# Main.net
KiCad netlist of a schematic drawn in Altium Designer
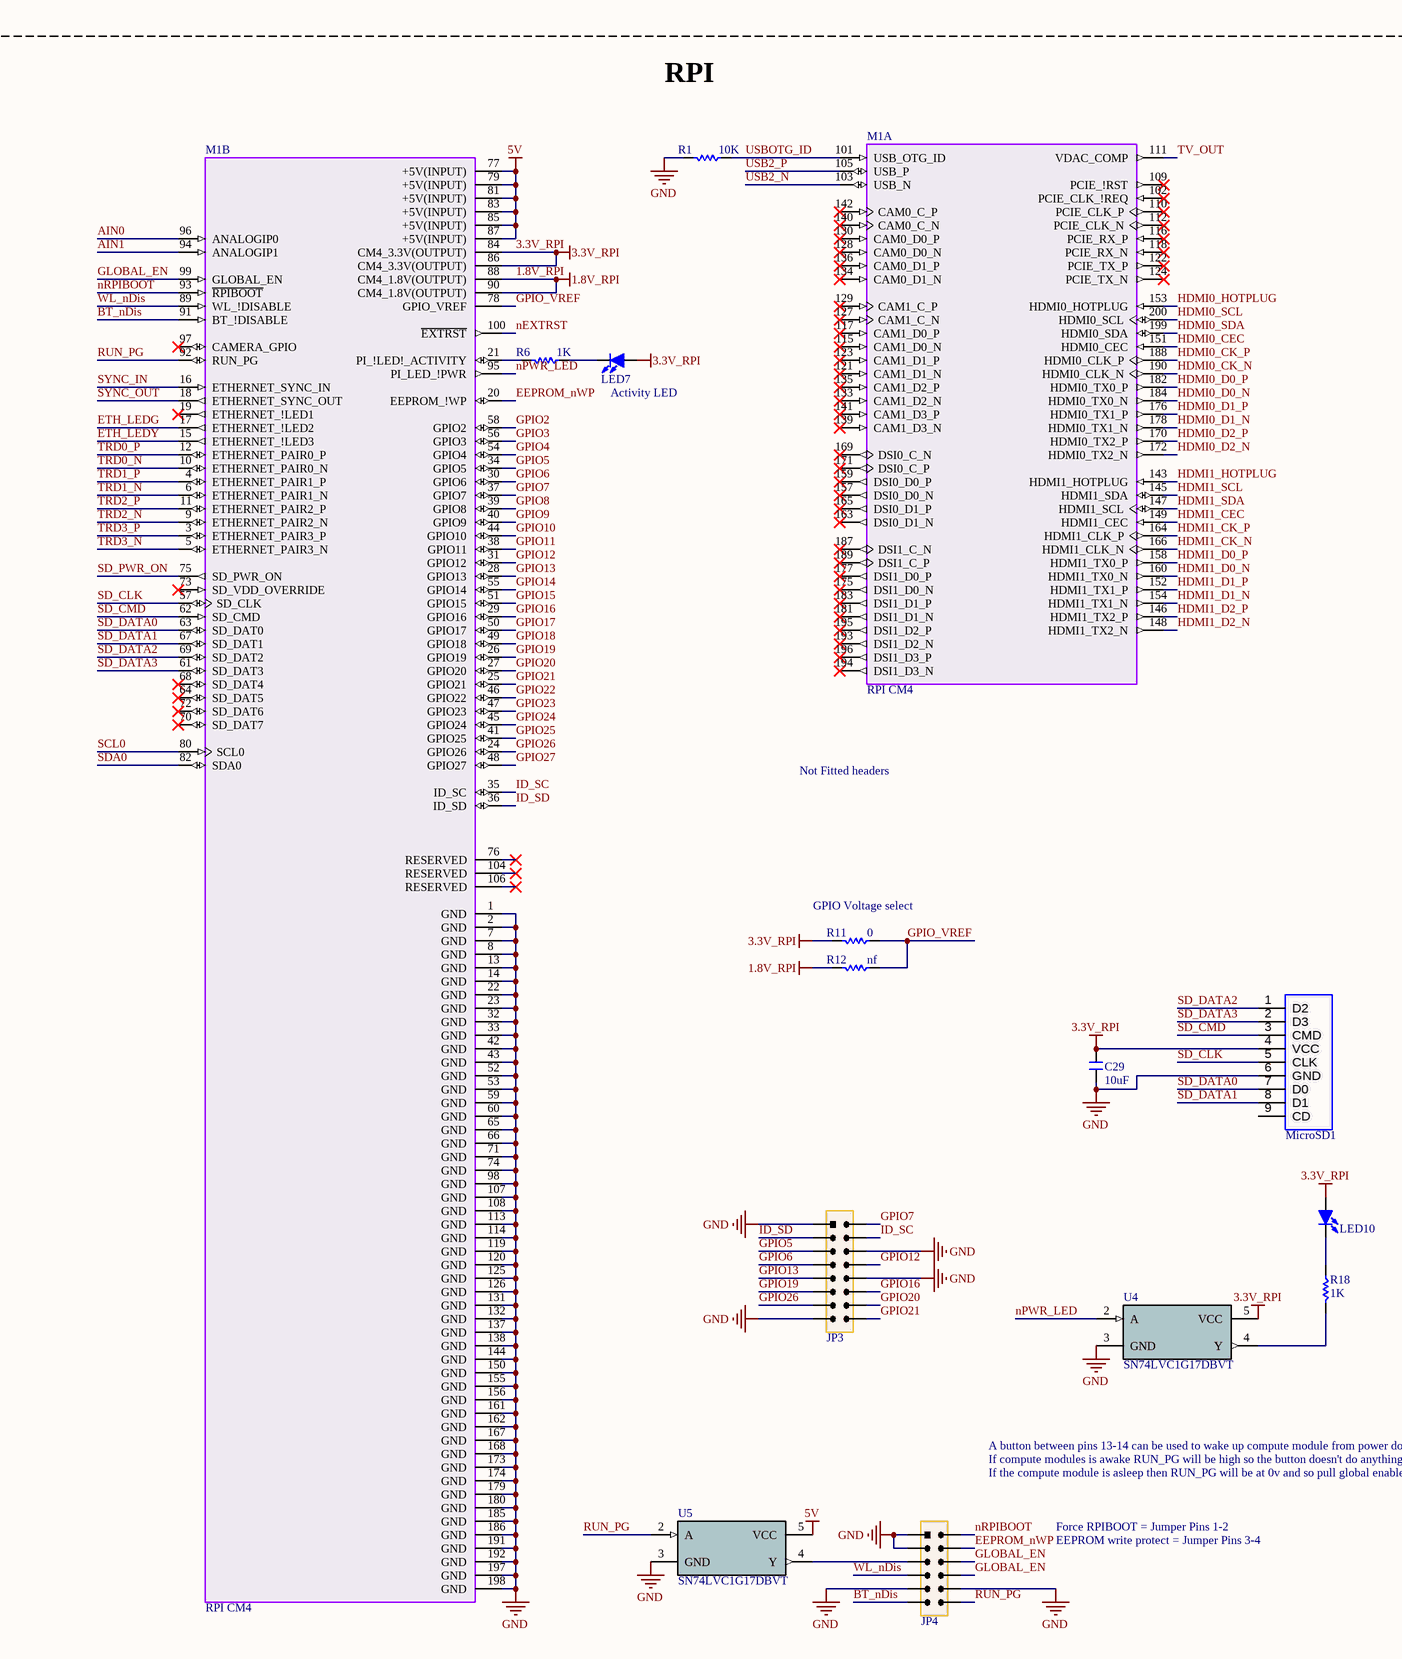
[diagram p0: Main.SchDoc, top left]
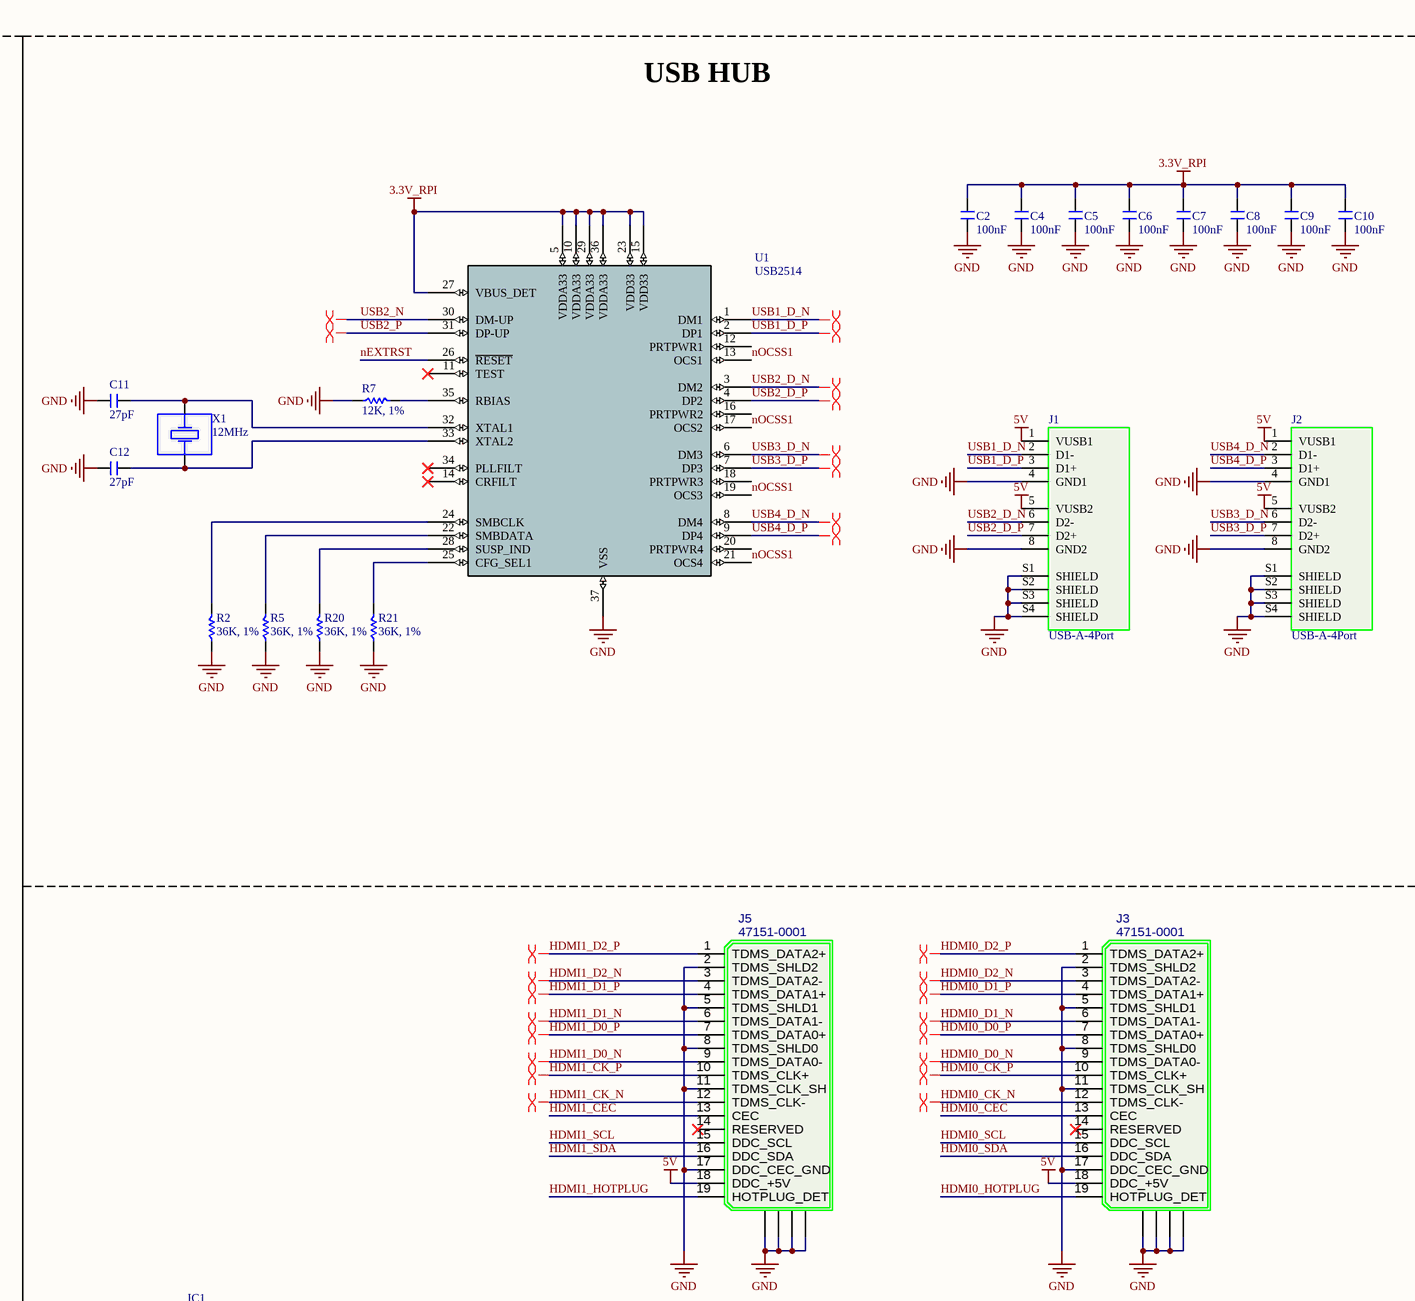
[diagram p1: Main.SchDoc, top middle]
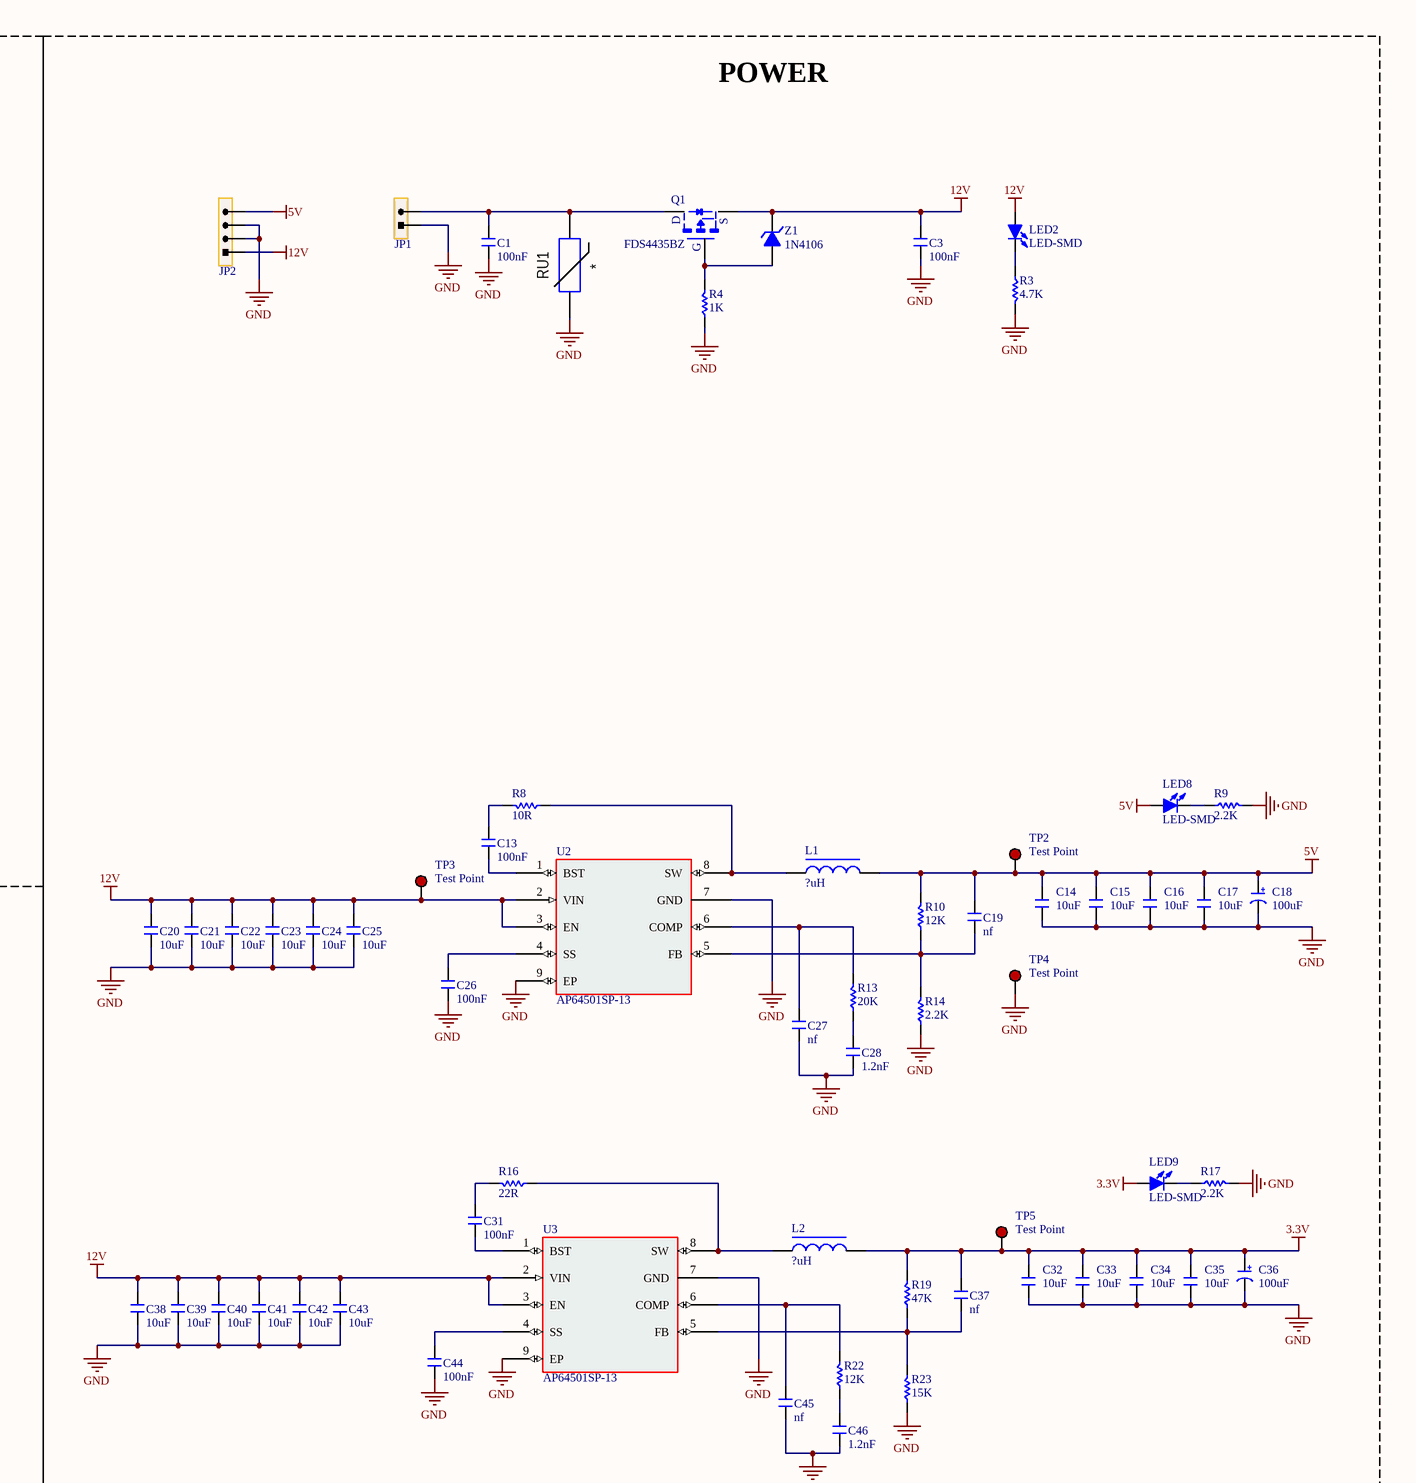
[diagram p2: Main.SchDoc, top right]
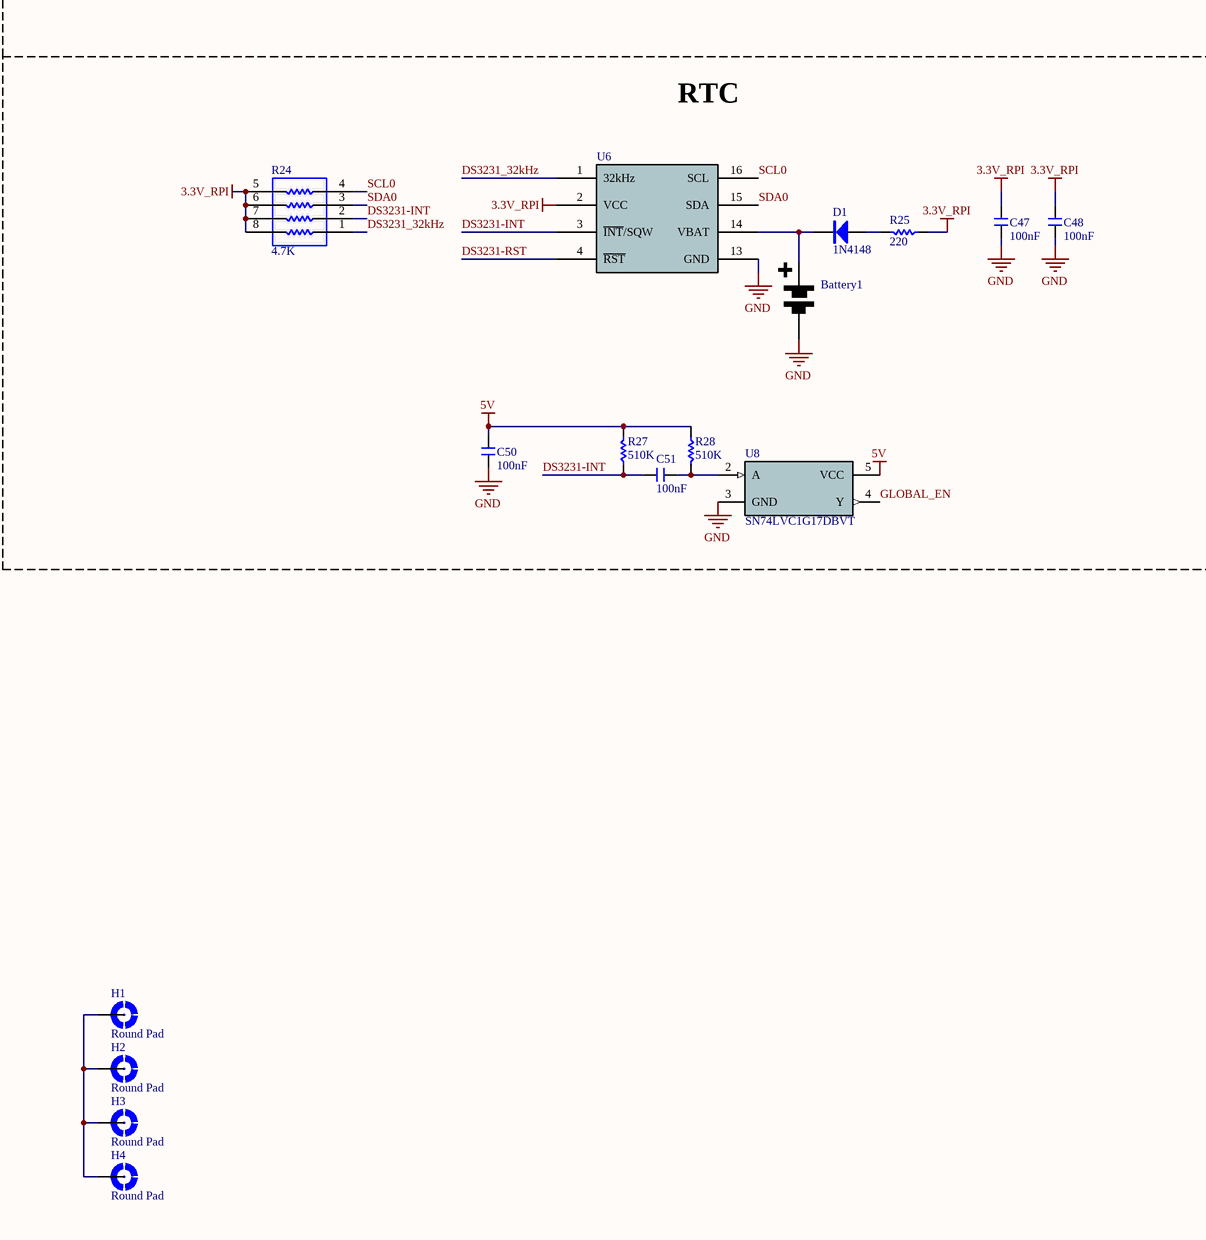
[diagram p3: Main.SchDoc, bottom left]
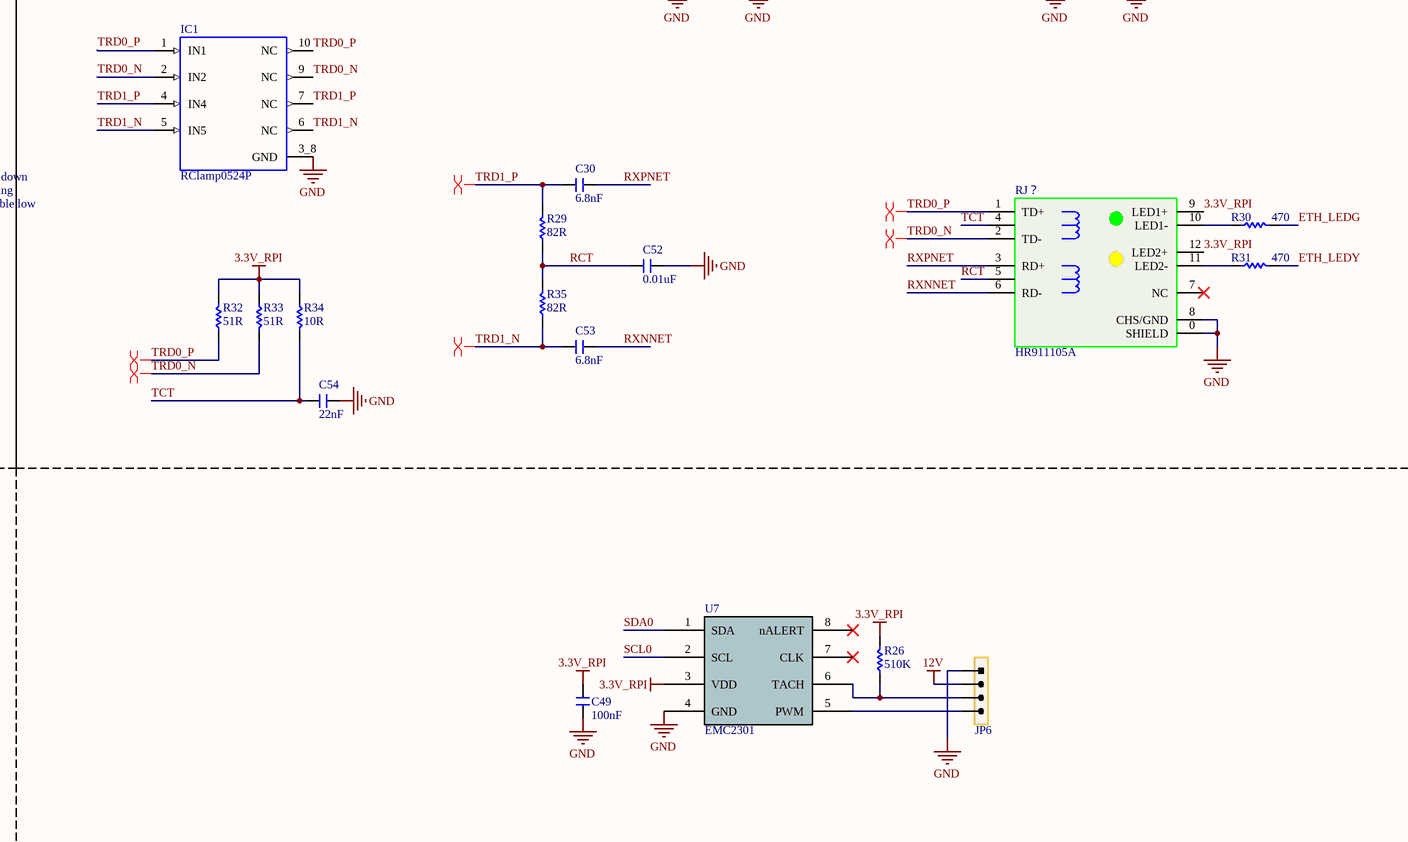
[diagram p4: Main.SchDoc, bottom middle]

(export (version "E")
  (design (tool "Eeschema 10.0.6"))
  (components
    (comp (ref "Battery1")
      (value "Battery Button Cell")
      (footprint "CR2032")
      (description "Mini Battery")
      (libsource (lib "Battery Holder") (part "Battery Button Cell"))
    )
    (comp (ref "C1")
      (value "100nF")
      (footprint "C 0805")
      (description "Non-polar patch capacitor")
      (fields (field (name "版权归属") "源创客"))
      (libsource (lib "") (part "C_1"))
    )
    (comp (ref "C2")
      (value "100nF")
      (footprint "C 0805")
      (description "Non-polar patch capacitor")
      (fields (field (name "版权归属") "源创客"))
      (libsource (lib "Passive (Resistor-Capacitor-Inductor-Veristor-Ferrite)") (part "C"))
    )
    (comp (ref "C3")
      (value "100nF")
      (footprint "C 0805")
      (description "Non-polar patch capacitor")
      (fields (field (name "版权归属") "源创客"))
      (libsource (lib "") (part "C_1"))
    )
    (comp (ref "C4")
      (value "100nF")
      (footprint "C 0805")
      (description "Non-polar patch capacitor")
      (fields (field (name "版权归属") "源创客"))
      (libsource (lib "Passive (Resistor-Capacitor-Inductor-Veristor-Ferrite)") (part "C"))
    )
    (comp (ref "C5")
      (value "100nF")
      (footprint "C 0805")
      (description "Non-polar patch capacitor")
      (fields (field (name "版权归属") "源创客"))
      (libsource (lib "Passive (Resistor-Capacitor-Inductor-Veristor-Ferrite)") (part "C"))
    )
    (comp (ref "C6")
      (value "100nF")
      (footprint "C 0805")
      (description "Non-polar patch capacitor")
      (fields (field (name "版权归属") "源创客"))
      (libsource (lib "Passive (Resistor-Capacitor-Inductor-Veristor-Ferrite)") (part "C"))
    )
    (comp (ref "C7")
      (value "100nF")
      (footprint "C 0805")
      (description "Non-polar patch capacitor")
      (fields (field (name "版权归属") "源创客"))
      (libsource (lib "Passive (Resistor-Capacitor-Inductor-Veristor-Ferrite)") (part "C"))
    )
    (comp (ref "C8")
      (value "100nF")
      (footprint "C 0805")
      (description "Non-polar patch capacitor")
      (fields (field (name "版权归属") "源创客"))
      (libsource (lib "Passive (Resistor-Capacitor-Inductor-Veristor-Ferrite)") (part "C"))
    )
    (comp (ref "C9")
      (value "100nF")
      (footprint "C 0805")
      (description "Non-polar patch capacitor")
      (fields (field (name "版权归属") "源创客"))
      (libsource (lib "Passive (Resistor-Capacitor-Inductor-Veristor-Ferrite)") (part "C"))
    )
    (comp (ref "C10")
      (value "100nF")
      (footprint "C 0805")
      (description "Non-polar patch capacitor")
      (fields (field (name "版权归属") "源创客"))
      (libsource (lib "Passive (Resistor-Capacitor-Inductor-Veristor-Ferrite)") (part "C"))
    )
    (comp (ref "C11")
      (value "27pF")
      (footprint "C 0805")
      (description "Non-polar patch capacitor")
      (fields (field (name "版权归属") "源创客"))
      (libsource (lib "Passive (Resistor-Capacitor-Inductor-Veristor-Ferrite)") (part "C"))
    )
    (comp (ref "C12")
      (value "27pF")
      (footprint "C 0805")
      (description "Non-polar patch capacitor")
      (fields (field (name "版权归属") "源创客"))
      (libsource (lib "Passive (Resistor-Capacitor-Inductor-Veristor-Ferrite)") (part "C"))
    )
    (comp (ref "C13")
      (value "100nF")
      (footprint "C 0805")
      (description "Non-polar patch capacitor")
      (fields (field (name "版权归属") "源创客"))
      (libsource (lib "") (part "C_1"))
    )
    (comp (ref "C14")
      (value "10uF")
      (footprint "C 0805")
      (description "Non-polar patch capacitor")
      (fields (field (name "版权归属") "源创客"))
      (libsource (lib "") (part "C_1"))
    )
    (comp (ref "C15")
      (value "10uF")
      (footprint "C 0805")
      (description "Non-polar patch capacitor")
      (fields (field (name "版权归属") "源创客"))
      (libsource (lib "") (part "C_1"))
    )
    (comp (ref "C16")
      (value "10uF")
      (footprint "C 0805")
      (description "Non-polar patch capacitor")
      (fields (field (name "版权归属") "源创客"))
      (libsource (lib "") (part "C_1"))
    )
    (comp (ref "C17")
      (value "10uF")
      (footprint "C 0805")
      (description "Non-polar patch capacitor")
      (fields (field (name "版权归属") "源创客"))
      (libsource (lib "") (part "C_1"))
    )
    (comp (ref "C18")
      (value "100uF")
      (footprint "CD D(7343)")
      (description "Solid Tantalum Chip Capacitor, Standard T491 Series - Industrial Grade")
      (fields (field (name "PUBLISHER") "Altium Limited"))
      (libsource (lib "Passive (Resistor-Capacitor-Inductor-Veristor-Ferrite)") (part "C-CD"))
    )
    (comp (ref "C19")
      (value "nf")
      (footprint "C 0805")
      (description "Non-polar patch capacitor")
      (fields (field (name "版权归属") "源创客"))
      (libsource (lib "") (part "C_1"))
    )
    (comp (ref "C20")
      (value "10uF")
      (footprint "C 0805")
      (description "Non-polar patch capacitor")
      (fields (field (name "版权归属") "源创客"))
      (libsource (lib "") (part "C_1"))
    )
    (comp (ref "C21")
      (value "10uF")
      (footprint "C 0805")
      (description "Non-polar patch capacitor")
      (fields (field (name "版权归属") "源创客"))
      (libsource (lib "") (part "C_1"))
    )
    (comp (ref "C22")
      (value "10uF")
      (footprint "C 0805")
      (description "Non-polar patch capacitor")
      (fields (field (name "版权归属") "源创客"))
      (libsource (lib "") (part "C_1"))
    )
    (comp (ref "C23")
      (value "10uF")
      (footprint "C 0805")
      (description "Non-polar patch capacitor")
      (fields (field (name "版权归属") "源创客"))
      (libsource (lib "") (part "C_1"))
    )
    (comp (ref "C24")
      (value "10uF")
      (footprint "C 0805")
      (description "Non-polar patch capacitor")
      (fields (field (name "版权归属") "源创客"))
      (libsource (lib "") (part "C_1"))
    )
    (comp (ref "C25")
      (value "10uF")
      (footprint "C 0805")
      (description "Non-polar patch capacitor")
      (fields (field (name "版权归属") "源创客"))
      (libsource (lib "") (part "C_1"))
    )
    (comp (ref "C26")
      (value "100nF")
      (footprint "C 0805")
      (description "Non-polar patch capacitor")
      (fields (field (name "版权归属") "源创客"))
      (libsource (lib "") (part "C_1"))
    )
    (comp (ref "C27")
      (value "nf")
      (footprint "C 0805")
      (description "Non-polar patch capacitor")
      (fields (field (name "版权归属") "源创客"))
      (libsource (lib "") (part "C_1"))
    )
    (comp (ref "C28")
      (value "1.2nF")
      (footprint "C 0805")
      (description "Non-polar patch capacitor")
      (fields (field (name "版权归属") "源创客"))
      (libsource (lib "") (part "C_1"))
    )
    (comp (ref "C29")
      (value "10uF")
      (footprint "C 0805")
      (description "Non-polar patch capacitor")
      (fields (field (name "版权归属") "源创客"))
      (libsource (lib "Passive (Resistor-Capacitor-Inductor-Veristor-Ferrite)") (part "C"))
    )
    (comp (ref "C30")
      (value "6.8nF")
      (footprint "C 0805")
      (description "Non-polar patch capacitor")
      (fields (field (name "版权归属") "源创客"))
      (libsource (lib "") (part "C_1"))
    )
    (comp (ref "C31")
      (value "100nF")
      (footprint "C 0805")
      (description "Non-polar patch capacitor")
      (fields (field (name "版权归属") "源创客"))
      (libsource (lib "") (part "C_1"))
    )
    (comp (ref "C32")
      (value "10uF")
      (footprint "C 0805")
      (description "Non-polar patch capacitor")
      (fields (field (name "版权归属") "源创客"))
      (libsource (lib "") (part "C_1"))
    )
    (comp (ref "C33")
      (value "10uF")
      (footprint "C 0805")
      (description "Non-polar patch capacitor")
      (fields (field (name "版权归属") "源创客"))
      (libsource (lib "") (part "C_1"))
    )
    (comp (ref "C34")
      (value "10uF")
      (footprint "C 0805")
      (description "Non-polar patch capacitor")
      (fields (field (name "版权归属") "源创客"))
      (libsource (lib "") (part "C_1"))
    )
    (comp (ref "C35")
      (value "10uF")
      (footprint "C 0805")
      (description "Non-polar patch capacitor")
      (fields (field (name "版权归属") "源创客"))
      (libsource (lib "") (part "C_1"))
    )
    (comp (ref "C36")
      (value "100uF")
      (footprint "CD D(7343)")
      (description "Solid Tantalum Chip Capacitor, Standard T491 Series - Industrial Grade")
      (fields (field (name "PUBLISHER") "Altium Limited"))
      (libsource (lib "Passive (Resistor-Capacitor-Inductor-Veristor-Ferrite)") (part "C-CD"))
    )
    (comp (ref "C37")
      (value "nf")
      (footprint "C 0805")
      (description "Non-polar patch capacitor")
      (fields (field (name "版权归属") "源创客"))
      (libsource (lib "") (part "C_1"))
    )
    (comp (ref "C38")
      (value "10uF")
      (footprint "C 0805")
      (description "Non-polar patch capacitor")
      (fields (field (name "版权归属") "源创客"))
      (libsource (lib "") (part "C_1"))
    )
    (comp (ref "C39")
      (value "10uF")
      (footprint "C 0805")
      (description "Non-polar patch capacitor")
      (fields (field (name "版权归属") "源创客"))
      (libsource (lib "") (part "C_1"))
    )
    (comp (ref "C40")
      (value "10uF")
      (footprint "C 0805")
      (description "Non-polar patch capacitor")
      (fields (field (name "版权归属") "源创客"))
      (libsource (lib "") (part "C_1"))
    )
    (comp (ref "C41")
      (value "10uF")
      (footprint "C 0805")
      (description "Non-polar patch capacitor")
      (fields (field (name "版权归属") "源创客"))
      (libsource (lib "") (part "C_1"))
    )
    (comp (ref "C42")
      (value "10uF")
      (footprint "C 0805")
      (description "Non-polar patch capacitor")
      (fields (field (name "版权归属") "源创客"))
      (libsource (lib "") (part "C_1"))
    )
    (comp (ref "C43")
      (value "10uF")
      (footprint "C 0805")
      (description "Non-polar patch capacitor")
      (fields (field (name "版权归属") "源创客"))
      (libsource (lib "") (part "C_1"))
    )
    (comp (ref "C44")
      (value "100nF")
      (footprint "C 0805")
      (description "Non-polar patch capacitor")
      (fields (field (name "版权归属") "源创客"))
      (libsource (lib "") (part "C_1"))
    )
    (comp (ref "C45")
      (value "nf")
      (footprint "C 0805")
      (description "Non-polar patch capacitor")
      (fields (field (name "版权归属") "源创客"))
      (libsource (lib "") (part "C_1"))
    )
    (comp (ref "C46")
      (value "1.2nF")
      (footprint "C 0805")
      (description "Non-polar patch capacitor")
      (fields (field (name "版权归属") "源创客"))
      (libsource (lib "") (part "C_1"))
    )
    (comp (ref "C47")
      (value "100nF")
      (footprint "C 0805")
      (description "Non-polar patch capacitor")
      (fields (field (name "版权归属") "源创客"))
      (libsource (lib "Passive (Resistor-Capacitor-Inductor-Veristor-Ferrite)") (part "C"))
    )
    (comp (ref "C48")
      (value "100nF")
      (footprint "C 0805")
      (description "Non-polar patch capacitor")
      (fields (field (name "版权归属") "源创客"))
      (libsource (lib "Passive (Resistor-Capacitor-Inductor-Veristor-Ferrite)") (part "C"))
    )
    (comp (ref "C49")
      (value "100nF")
      (footprint "C 0805")
      (description "Non-polar patch capacitor")
      (fields (field (name "版权归属") "源创客"))
      (libsource (lib "Passive (Resistor-Capacitor-Inductor-Veristor-Ferrite)") (part "C"))
    )
    (comp (ref "C50")
      (value "100nF")
      (footprint "C 0805")
      (description "Non-polar patch capacitor")
      (fields (field (name "版权归属") "源创客"))
      (libsource (lib "Passive (Resistor-Capacitor-Inductor-Veristor-Ferrite)") (part "C"))
    )
    (comp (ref "C51")
      (value "100nF")
      (footprint "C 0805")
      (description "Non-polar patch capacitor")
      (fields (field (name "版权归属") "源创客"))
      (libsource (lib "Passive (Resistor-Capacitor-Inductor-Veristor-Ferrite)") (part "C"))
    )
    (comp (ref "C52")
      (value "0.01uF")
      (footprint "C 0805")
      (description "Non-polar patch capacitor")
      (fields (field (name "版权归属") "源创客"))
      (libsource (lib "") (part "C_1"))
    )
    (comp (ref "C53")
      (value "6.8nF")
      (footprint "C 0805")
      (description "Non-polar patch capacitor")
      (fields (field (name "版权归属") "源创客"))
      (libsource (lib "") (part "C_1"))
    )
    (comp (ref "C54")
      (value "22nF")
      (footprint "C 0805")
      (description "Non-polar patch capacitor")
      (fields (field (name "版权归属") "源创客"))
      (libsource (lib "") (part "C_1"))
    )
    (comp (ref "D1")
      (value "1N4148")
      (footprint "MINI_MELF (LL34)")
      (description "High speed switching diode")
      (fields (field (name "版权归属") "源创客"))
      (libsource (lib "Diode-Zener-Rectifier Bridge") (part "1N4148"))
    )
    (comp (ref "H1")
      (value "Round Pad")
      (footprint "P3.2C")
      (description "MOUNTING PAD, round")
      (libsource (lib "Mechanical Components") (part "MOUNT-PAD-ROUND"))
    )
    (comp (ref "H2")
      (value "Round Pad")
      (footprint "P3.2C")
      (description "MOUNTING PAD, round")
      (libsource (lib "Mechanical Components") (part "MOUNT-PAD-ROUND"))
    )
    (comp (ref "H3")
      (value "Round Pad")
      (footprint "P3.2C")
      (description "MOUNTING PAD, round")
      (libsource (lib "Mechanical Components") (part "MOUNT-PAD-ROUND"))
    )
    (comp (ref "H4")
      (value "Round Pad")
      (footprint "P3.2C")
      (description "MOUNTING PAD, round")
      (libsource (lib "Mechanical Components") (part "MOUNT-PAD-ROUND"))
    )
    (comp (ref "IC1")
      (value "RClamp0524P")
      (footprint "RClamp0524P")
      (libsource (lib "Diode-Zener-Rectifier Bridge") (part "RClamp0524P"))
    )
    (comp (ref "J1")
      (value "USB-A-4Port")
      (footprint "USB-A-4Port")
      (libsource (lib "IO (Power-USB-Serial-VGA-RJ-Audio-Buzzer)") (part "USB-A-4Port"))
    )
    (comp (ref "J2")
      (value "USB-A-4Port")
      (footprint "USB-A-4Port")
      (libsource (lib "IO (Power-USB-Serial-VGA-RJ-Audio-Buzzer)") (part "USB-A-4Port"))
    )
    (comp (ref "J3")
      (value "47151-0001")
      (footprint "HDMI-A")
      (description "CONNECTOR, HDMI TYPE A, R/A, SMD")
      (fields (field (name "MANUFACTURER") "MOLEX"))
      (libsource (lib "IO (Power-USB-Serial-VGA-RJ-Audio-Buzzer)") (part "HDMI-A"))
    )
    (comp (ref "J5")
      (value "47151-0001")
      (footprint "HDMI-A")
      (description "CONNECTOR, HDMI TYPE A, R/A, SMD")
      (fields (field (name "MANUFACTURER") "MOLEX"))
      (libsource (lib "IO (Power-USB-Serial-VGA-RJ-Audio-Buzzer)") (part "HDMI-A"))
    )
    (comp (ref "JP1")
      (value "HDR-1X2")
      (footprint "KF2EDGK-2P_H_5.08")
      (description "2P Connector")
      (fields (field (name "版权归属") "源创客"))
      (libsource (lib "Connectors") (part "Header 2"))
    )
    (comp (ref "JP2")
      (value "HDR-1X4")
      (footprint "KF2EDGK-4P_H_5.08")
      (description "4P Connector")
      (fields (field (name "版权归属") "源创客"))
      (libsource (lib "Connectors") (part "Header 4"))
    )
    (comp (ref "JP3")
      (value "Header 8X2")
      (footprint "HDR-8X2")
      (description "8*2P Connector")
      (fields (field (name "版权归属") "源创客"))
      (libsource (lib "Connectors") (part "Header 8X2"))
    )
    (comp (ref "JP4")
      (value "Header 6X2")
      (footprint "HDR-6X2")
      (description "6*2P Connector")
      (fields (field (name "版权归属") "源创客"))
      (libsource (lib "Connectors") (part "Header  6X2"))
    )
    (comp (ref "JP6")
      (value "HDR-1X4")
      (footprint "KF2EDGK-4P_H_5.08")
      (description "4P Connector")
      (fields (field (name "版权归属") "源创客"))
      (libsource (lib "") (part "Header 4_1"))
    )
    (comp (ref "L1")
      (value "?uH")
      (footprint "CD53")
      (description "Chip power inductor")
      (fields (field (name "版权归属") "源创客"))
      (libsource (lib "Passive (Resistor-Capacitor-Inductor-Veristor-Ferrite)") (part "L-CD"))
    )
    (comp (ref "L2")
      (value "?uH")
      (footprint "CD53")
      (description "Chip power inductor")
      (fields (field (name "版权归属") "源创客"))
      (libsource (lib "Passive (Resistor-Capacitor-Inductor-Veristor-Ferrite)") (part "L-CD"))
    )
    (comp (ref "LED2")
      (value "LED-SMD")
      (footprint "LED 0805R")
      (description "Patch LED")
      (fields (field (name "版权归属") "源创客"))
      (libsource (lib "LED") (part "LED-SMD"))
    )
    (comp (ref "LED7")
      (value "LED GREEN")
      (footprint "LED 0805R")
      (description "Patch LED")
      (fields (field (name "版权归属") "源创客"))
      (libsource (lib "LED") (part "LED-SMD"))
    )
    (comp (ref "LED8")
      (value "LED-SMD")
      (footprint "LED 0805R")
      (description "Patch LED")
      (fields (field (name "版权归属") "源创客"))
      (libsource (lib "LED") (part "LED-SMD"))
    )
    (comp (ref "LED9")
      (value "LED-SMD")
      (footprint "LED 0805R")
      (description "Patch LED")
      (fields (field (name "版权归属") "源创客"))
      (libsource (lib "LED") (part "LED-SMD"))
    )
    (comp (ref "LED10")
      (value "LED RED")
      (footprint "LED 0805R")
      (description "Patch LED")
      (fields (field (name "版权归属") "源创客"))
      (libsource (lib "LED") (part "LED-SMD"))
    )
    (comp (ref "M1") (value "RPI CM4") (footprint "CM4") (libsource (lib "Raspberry pi") (part "CM4")))
    (comp (ref "MicroSD1")
      (value "MicroSD Card")
      (footprint "micro SD Card")
      (description "MicroSD")
      (libsource (lib "SDCard-SIMCard") (part "MicroSD Card"))
    )
    (comp (ref "Q1")
      (value "FDS4435BZ")
      (footprint "SOP8-E3")
      (libsource (lib "Transistor") (part "FDS4435BZ"))
    )
    (comp (ref "R1")
      (value "10K")
      (footprint "R 0805")
      (description "Chip resistor")
      (fields (field (name "版权归属") "源创客"))
      (libsource (lib "Passive (Resistor-Capacitor-Inductor-Veristor-Ferrite)") (part "R"))
    )
    (comp (ref "R2")
      (value "36K, 1%")
      (footprint "R 0805")
      (description "Chip resistor")
      (fields (field (name "版权归属") "源创客"))
      (libsource (lib "Passive (Resistor-Capacitor-Inductor-Veristor-Ferrite)") (part "R"))
    )
    (comp (ref "R3")
      (value "4.7K")
      (footprint "R 0805")
      (description "Chip resistor")
      (fields (field (name "版权归属") "源创客"))
      (libsource (lib "Passive (Resistor-Capacitor-Inductor-Veristor-Ferrite)") (part "R"))
    )
    (comp (ref "R4")
      (value "1K")
      (footprint "R 0805")
      (description "Chip resistor")
      (fields (field (name "版权归属") "源创客"))
      (libsource (lib "Passive (Resistor-Capacitor-Inductor-Veristor-Ferrite)") (part "R"))
    )
    (comp (ref "R5")
      (value "36K, 1%")
      (footprint "R 0805")
      (description "Chip resistor")
      (fields (field (name "版权归属") "源创客"))
      (libsource (lib "Passive (Resistor-Capacitor-Inductor-Veristor-Ferrite)") (part "R"))
    )
    (comp (ref "R6")
      (value "1K")
      (footprint "R 0805")
      (description "Chip resistor")
      (fields (field (name "版权归属") "源创客"))
      (libsource (lib "Passive (Resistor-Capacitor-Inductor-Veristor-Ferrite)") (part "R"))
    )
    (comp (ref "R7")
      (value "12K, 1%")
      (footprint "R 0805")
      (description "Chip resistor")
      (fields (field (name "版权归属") "源创客"))
      (libsource (lib "Passive (Resistor-Capacitor-Inductor-Veristor-Ferrite)") (part "R"))
    )
    (comp (ref "R8")
      (value "10R")
      (footprint "R 0805")
      (description "Chip resistor")
      (fields (field (name "版权归属") "源创客"))
      (libsource (lib "Passive (Resistor-Capacitor-Inductor-Veristor-Ferrite)") (part "R"))
    )
    (comp (ref "R9")
      (value "2.2K")
      (footprint "R 0805")
      (description "Chip resistor")
      (fields (field (name "版权归属") "源创客"))
      (libsource (lib "Passive (Resistor-Capacitor-Inductor-Veristor-Ferrite)") (part "R"))
    )
    (comp (ref "R10")
      (value "12K")
      (footprint "R 0805")
      (description "Chip resistor")
      (fields (field (name "版权归属") "源创客"))
      (libsource (lib "Passive (Resistor-Capacitor-Inductor-Veristor-Ferrite)") (part "R"))
    )
    (comp (ref "R11")
      (value "0")
      (footprint "R 0805")
      (description "Chip resistor")
      (fields (field (name "版权归属") "源创客"))
      (libsource (lib "Passive (Resistor-Capacitor-Inductor-Veristor-Ferrite)") (part "R"))
    )
    (comp (ref "R12")
      (value "nf")
      (footprint "R 0805")
      (description "Chip resistor")
      (fields (field (name "版权归属") "源创客"))
      (libsource (lib "Passive (Resistor-Capacitor-Inductor-Veristor-Ferrite)") (part "R"))
    )
    (comp (ref "R13")
      (value "20K")
      (footprint "R 0805")
      (description "Chip resistor")
      (fields (field (name "版权归属") "源创客"))
      (libsource (lib "Passive (Resistor-Capacitor-Inductor-Veristor-Ferrite)") (part "R"))
    )
    (comp (ref "R14")
      (value "2.2K")
      (footprint "R 0805")
      (description "Chip resistor")
      (fields (field (name "版权归属") "源创客"))
      (libsource (lib "Passive (Resistor-Capacitor-Inductor-Veristor-Ferrite)") (part "R"))
    )
    (comp (ref "R16")
      (value "22R")
      (footprint "R 0805")
      (description "Chip resistor")
      (fields (field (name "版权归属") "源创客"))
      (libsource (lib "Passive (Resistor-Capacitor-Inductor-Veristor-Ferrite)") (part "R"))
    )
    (comp (ref "R17")
      (value "2.2K")
      (footprint "R 0805")
      (description "Chip resistor")
      (fields (field (name "版权归属") "源创客"))
      (libsource (lib "Passive (Resistor-Capacitor-Inductor-Veristor-Ferrite)") (part "R"))
    )
    (comp (ref "R18")
      (value "1K")
      (footprint "R 0805")
      (description "Chip resistor")
      (fields (field (name "版权归属") "源创客"))
      (libsource (lib "Passive (Resistor-Capacitor-Inductor-Veristor-Ferrite)") (part "R"))
    )
    (comp (ref "R19")
      (value "47K")
      (footprint "R 0805")
      (description "Chip resistor")
      (fields (field (name "版权归属") "源创客"))
      (libsource (lib "Passive (Resistor-Capacitor-Inductor-Veristor-Ferrite)") (part "R"))
    )
    (comp (ref "R20")
      (value "36K, 1%")
      (footprint "R 0805")
      (description "Chip resistor")
      (fields (field (name "版权归属") "源创客"))
      (libsource (lib "Passive (Resistor-Capacitor-Inductor-Veristor-Ferrite)") (part "R"))
    )
    (comp (ref "R21")
      (value "36K, 1%")
      (footprint "R 0805")
      (description "Chip resistor")
      (fields (field (name "版权归属") "源创客"))
      (libsource (lib "Passive (Resistor-Capacitor-Inductor-Veristor-Ferrite)") (part "R"))
    )
    (comp (ref "R22")
      (value "12K")
      (footprint "R 0805")
      (description "Chip resistor")
      (fields (field (name "版权归属") "源创客"))
      (libsource (lib "Passive (Resistor-Capacitor-Inductor-Veristor-Ferrite)") (part "R"))
    )
    (comp (ref "R23")
      (value "15K")
      (footprint "R 0805")
      (description "Chip resistor")
      (fields (field (name "版权归属") "源创客"))
      (libsource (lib "Passive (Resistor-Capacitor-Inductor-Veristor-Ferrite)") (part "R"))
    )
    (comp (ref "R24")
      (value "4.7K")
      (footprint "RA1206 (4x0603)")
      (description "4 way Chip Resistor Array")
      (libsource (lib "Passive (Resistor-Capacitor-Inductor-Veristor-Ferrite)") (part "R-ARR"))
    )
    (comp (ref "R25")
      (value "220")
      (footprint "R 0805")
      (description "Chip resistor")
      (fields (field (name "版权归属") "源创客"))
      (libsource (lib "Passive (Resistor-Capacitor-Inductor-Veristor-Ferrite)") (part "R"))
    )
    (comp (ref "R26")
      (value "510K")
      (footprint "R 0805")
      (description "Chip resistor")
      (fields (field (name "版权归属") "源创客"))
      (libsource (lib "Passive (Resistor-Capacitor-Inductor-Veristor-Ferrite)") (part "R"))
    )
    (comp (ref "R27")
      (value "510K")
      (footprint "R 0805")
      (description "Chip resistor")
      (fields (field (name "版权归属") "源创客"))
      (libsource (lib "Passive (Resistor-Capacitor-Inductor-Veristor-Ferrite)") (part "R"))
    )
    (comp (ref "R28")
      (value "510K")
      (footprint "R 0805")
      (description "Chip resistor")
      (fields (field (name "版权归属") "源创客"))
      (libsource (lib "Passive (Resistor-Capacitor-Inductor-Veristor-Ferrite)") (part "R"))
    )
    (comp (ref "R29")
      (value "82R")
      (footprint "R 0805")
      (description "Chip resistor")
      (fields (field (name "版权归属") "源创客"))
      (libsource (lib "Passive (Resistor-Capacitor-Inductor-Veristor-Ferrite)") (part "R"))
    )
    (comp (ref "R30")
      (value "470")
      (footprint "R 0805")
      (description "Chip resistor")
      (fields (field (name "版权归属") "源创客"))
      (libsource (lib "Passive (Resistor-Capacitor-Inductor-Veristor-Ferrite)") (part "R"))
    )
    (comp (ref "R31")
      (value "470")
      (footprint "R 0805")
      (description "Chip resistor")
      (fields (field (name "版权归属") "源创客"))
      (libsource (lib "Passive (Resistor-Capacitor-Inductor-Veristor-Ferrite)") (part "R"))
    )
    (comp (ref "R32")
      (value "51R")
      (footprint "R 0805")
      (description "Chip resistor")
      (fields (field (name "版权归属") "源创客"))
      (libsource (lib "Passive (Resistor-Capacitor-Inductor-Veristor-Ferrite)") (part "R"))
    )
    (comp (ref "R33")
      (value "51R")
      (footprint "R 0805")
      (description "Chip resistor")
      (fields (field (name "版权归属") "源创客"))
      (libsource (lib "Passive (Resistor-Capacitor-Inductor-Veristor-Ferrite)") (part "R"))
    )
    (comp (ref "R34")
      (value "10R")
      (footprint "R 0805")
      (description "Chip resistor")
      (fields (field (name "版权归属") "源创客"))
      (libsource (lib "Passive (Resistor-Capacitor-Inductor-Veristor-Ferrite)") (part "R"))
    )
    (comp (ref "R35")
      (value "82R")
      (footprint "R 0805")
      (description "Chip resistor")
      (fields (field (name "版权归属") "源创客"))
      (libsource (lib "Passive (Resistor-Capacitor-Inductor-Veristor-Ferrite)") (part "R"))
    )
    (comp (ref "RJ？")
      (value "HR911105A")
      (footprint "RJ-45A12")
      (description "Illuminated Ethernet interface")
      (fields (field (name "版权归属") "源创客"))
      (libsource (lib "IO (Power-USB-Serial-VGA-RJ-Audio-Buzzer)") (part "HR911105A"))
    )
    (comp (ref "RU1")
      (value "*")
      (footprint "SMA")
      (description "Versiror")
      (libsource (lib "Passive (Resistor-Capacitor-Inductor-Veristor-Ferrite)") (part "V"))
    )
    (comp (ref "TP2")
      (value "Test Point")
      (footprint "TEST_POINT_40MIL_R")
      (libsource (lib "Test Point") (part "Test Point"))
    )
    (comp (ref "TP3")
      (value "Test Point")
      (footprint "TEST_POINT_40MIL_R")
      (libsource (lib "Test Point") (part "Test Point"))
    )
    (comp (ref "TP4")
      (value "Test Point")
      (footprint "TEST_POINT_40MIL_R")
      (libsource (lib "Test Point") (part "Test Point"))
    )
    (comp (ref "TP5")
      (value "Test Point")
      (footprint "TEST_POINT_40MIL_R")
      (libsource (lib "Test Point") (part "Test Point"))
    )
    (comp (ref "U1")
      (value "USB2514")
      (footprint "QFN36")
      (libsource (lib "Integrated Circuit") (part "USB2514"))
    )
    (comp (ref "U2")
      (value "AP64501SP-13")
      (footprint "SOP8_M-EP")
      (libsource (lib "Integrated Circuit") (part "AP64501SP-13"))
    )
    (comp (ref "U3")
      (value "AP64501SP-13")
      (footprint "SOP8_M-EP")
      (libsource (lib "Integrated Circuit") (part "AP64501SP-13"))
    )
    (comp (ref "U4")
      (value "SN74LVC1G17DBVT")
      (footprint "SOT23-5M")
      (description "Single 1.65-V to 5.5-V buffer with Schmitt-Trigger inputs")
      (libsource (lib "Integrated Circuit") (part "SN74LVC1G17DBVT"))
    )
    (comp (ref "U5")
      (value "SN74LVC1G17DBVT")
      (footprint "SOT23-5M")
      (description "Single 1.65-V to 5.5-V buffer with Schmitt-Trigger inputs")
      (libsource (lib "Integrated Circuit") (part "SN74LVC1G17DBVT"))
    )
    (comp (ref "U6")
      (value "DS3231")
      (footprint "SOP16W_L")
      (description "Real time clock chip")
      (libsource (lib "Integrated Circuit") (part "DS3231"))
    )
    (comp (ref "U7")
      (value "EMC2301")
      (footprint "MSOP-8")
      (description "PWM Fan Controller")
      (libsource (lib "Integrated Circuit") (part "EMC2301"))
    )
    (comp (ref "U8")
      (value "SN74LVC1G17DBVT")
      (footprint "SOT23-5M")
      (description "Single 1.65-V to 5.5-V buffer with Schmitt-Trigger inputs")
      (libsource (lib "Integrated Circuit") (part "SN74LVC1G17DBVT"))
    )
    (comp (ref "X1")
      (value "12MHz")
      (footprint "XTAL-HC49S-SMD")
      (description "2-Pin crystal")
      (fields (field (name "版权归属") "源创客"))
      (libsource (lib "Crystal Oscillator") (part "XTAL-2"))
    )
    (comp (ref "Z1")
      (value "1N4106")
      (footprint "DO-213AA")
      (description "12V/0.5W voltage regulator")
      (fields (field (name "版权归属") "源创客"))
      (libsource (lib "Diode-Zener-Rectifier Bridge") (part "1N4106"))
    )
  )
  (nets
    (net (code "1") (name "/AIN0") (class "Default")
      (node (ref "M1") (pin "96") (pinfunction "ANALOGIP0_96") (pintype "input"))
    )
    (net (code "2") (name "/AIN1") (class "Default")
      (node (ref "M1") (pin "94") (pinfunction "ANALOGIP1_94") (pintype "input"))
    )
    (net (code "3") (name "/BT_nDis") (class "Default")
      (node (ref "JP4") (pin "11") (pintype "passive"))
      (node (ref "M1") (pin "91") (pinfunction "BT_!DISABLE_91") (pintype "input"))
    )
    (net (code "4") (name "/DS3231-INT") (class "Default")
      (node (ref "C51") (pin "2") (pinfunction "2_2") (pintype "passive"))
      (node (ref "R24") (pin "2") (pinfunction "2_2") (pintype "passive"))
      (node (ref "R27") (pin "1") (pinfunction "1_1") (pintype "passive"))
      (node (ref "U6") (pin "3") (pinfunction "~{INT}/SQW_3") (pintype "passive"))
    )
    (net (code "5") (name "/DS3231-RST") (class "Default")
      (node (ref "U6") (pin "4") (pinfunction "~{RST}_4") (pintype "passive"))
    )
    (net (code "6") (name "/DS3231_32kHz") (class "Default")
      (node (ref "R24") (pin "1") (pinfunction "1_1") (pintype "passive"))
      (node (ref "U6") (pin "1") (pinfunction "32kHz_1") (pintype "passive"))
    )
    (net (code "7") (name "/EEPROM_nWP") (class "Default")
      (node (ref "JP4") (pin "4") (pintype "passive"))
      (node (ref "M1") (pin "20") (pinfunction "EEPROM_!WP_20") (pintype "bidirectional"))
    )
    (net (code "8") (name "/ETH_LEDG") (class "Default")
      (node (ref "M1") (pin "17") (pinfunction "ETHERNET_!LED2_17") (pintype "output"))
      (node (ref "R30") (pin "2") (pinfunction "2_2") (pintype "passive"))
    )
    (net (code "9") (name "/ETH_LEDY") (class "Default")
      (node (ref "M1") (pin "15") (pinfunction "ETHERNET_!LED3_15") (pintype "output"))
      (node (ref "R31") (pin "2") (pinfunction "2_2") (pintype "passive"))
    )
    (net (code "10") (name "/GLOBAL_EN") (class "Default")
      (node (ref "JP4") (pin "6") (pintype "passive"))
      (node (ref "JP4") (pin "8") (pintype "passive"))
      (node (ref "M1") (pin "99") (pinfunction "GLOBAL_EN_99") (pintype "input"))
      (node (ref "U8") (pin "4") (pinfunction "Y_4") (pintype "output"))
    )
    (net (code "11") (name "/GPIO2") (class "Default")
      (node (ref "M1") (pin "58") (pinfunction "GPIO2_58") (pintype "bidirectional"))
    )
    (net (code "12") (name "/GPIO3") (class "Default")
      (node (ref "M1") (pin "56") (pinfunction "GPIO3_56") (pintype "bidirectional"))
    )
    (net (code "13") (name "/GPIO4") (class "Default")
      (node (ref "M1") (pin "54") (pinfunction "GPIO4_54") (pintype "bidirectional"))
    )
    (net (code "14") (name "/GPIO5") (class "Default")
      (node (ref "JP3") (pin "5") (pintype "passive"))
      (node (ref "M1") (pin "34") (pinfunction "GPIO5_34") (pintype "bidirectional"))
    )
    (net (code "15") (name "/GPIO6") (class "Default")
      (node (ref "JP3") (pin "7") (pintype "passive"))
      (node (ref "M1") (pin "30") (pinfunction "GPIO6_30") (pintype "bidirectional"))
    )
    (net (code "16") (name "/GPIO7") (class "Default")
      (node (ref "JP3") (pin "2") (pintype "passive"))
      (node (ref "M1") (pin "37") (pinfunction "GPIO7_37") (pintype "bidirectional"))
    )
    (net (code "17") (name "/GPIO8") (class "Default")
      (node (ref "M1") (pin "39") (pinfunction "GPIO8_39") (pintype "bidirectional"))
    )
    (net (code "18") (name "/GPIO9") (class "Default")
      (node (ref "M1") (pin "40") (pinfunction "GPIO9_40") (pintype "bidirectional"))
    )
    (net (code "19") (name "/GPIO10") (class "Default")
      (node (ref "M1") (pin "44") (pinfunction "GPIO10_44") (pintype "bidirectional"))
    )
    (net (code "20") (name "/GPIO11") (class "Default")
      (node (ref "M1") (pin "38") (pinfunction "GPIO11_38") (pintype "bidirectional"))
    )
    (net (code "21") (name "/GPIO12") (class "Default")
      (node (ref "JP3") (pin "8") (pintype "passive"))
      (node (ref "M1") (pin "31") (pinfunction "GPIO12_31") (pintype "bidirectional"))
    )
    (net (code "22") (name "/GPIO13") (class "Default")
      (node (ref "JP3") (pin "9") (pintype "passive"))
      (node (ref "M1") (pin "28") (pinfunction "GPIO13_28") (pintype "bidirectional"))
    )
    (net (code "23") (name "/GPIO14") (class "Default")
      (node (ref "M1") (pin "55") (pinfunction "GPIO14_55") (pintype "bidirectional"))
    )
    (net (code "24") (name "/GPIO15") (class "Default")
      (node (ref "M1") (pin "51") (pinfunction "GPIO15_51") (pintype "bidirectional"))
    )
    (net (code "25") (name "/GPIO16") (class "Default")
      (node (ref "JP3") (pin "12") (pintype "passive"))
      (node (ref "M1") (pin "29") (pinfunction "GPIO16_29") (pintype "bidirectional"))
    )
    (net (code "26") (name "/GPIO17") (class "Default")
      (node (ref "M1") (pin "50") (pinfunction "GPIO17_50") (pintype "bidirectional"))
    )
    (net (code "27") (name "/GPIO18") (class "Default")
      (node (ref "M1") (pin "49") (pinfunction "GPIO18_49") (pintype "bidirectional"))
    )
    (net (code "28") (name "/GPIO19") (class "Default")
      (node (ref "JP3") (pin "11") (pintype "passive"))
      (node (ref "M1") (pin "26") (pinfunction "GPIO19_26") (pintype "bidirectional"))
    )
    (net (code "29") (name "/GPIO20") (class "Default")
      (node (ref "JP3") (pin "14") (pintype "passive"))
      (node (ref "M1") (pin "27") (pinfunction "GPIO20_27") (pintype "bidirectional"))
    )
    (net (code "30") (name "/GPIO21") (class "Default")
      (node (ref "JP3") (pin "16") (pintype "passive"))
      (node (ref "M1") (pin "25") (pinfunction "GPIO21_25") (pintype "bidirectional"))
    )
    (net (code "31") (name "/GPIO22") (class "Default")
      (node (ref "M1") (pin "46") (pinfunction "GPIO22_46") (pintype "bidirectional"))
    )
    (net (code "32") (name "/GPIO23") (class "Default")
      (node (ref "M1") (pin "47") (pinfunction "GPIO23_47") (pintype "bidirectional"))
    )
    (net (code "33") (name "/GPIO24") (class "Default")
      (node (ref "M1") (pin "45") (pinfunction "GPIO24_45") (pintype "bidirectional"))
    )
    (net (code "34") (name "/GPIO25") (class "Default")
      (node (ref "M1") (pin "41") (pinfunction "GPIO25_41") (pintype "bidirectional"))
    )
    (net (code "35") (name "/GPIO26") (class "Default")
      (node (ref "JP3") (pin "13") (pintype "passive"))
      (node (ref "M1") (pin "24") (pinfunction "GPIO26_24") (pintype "bidirectional"))
    )
    (net (code "36") (name "/GPIO27") (class "Default")
      (node (ref "M1") (pin "48") (pinfunction "GPIO27_48") (pintype "bidirectional"))
    )
    (net (code "37") (name "/GPIO_VREF") (class "Default")
      (node (ref "M1") (pin "78") (pinfunction "GPIO_VREF_78") (pintype "power_in"))
      (node (ref "R11") (pin "1") (pinfunction "1_1") (pintype "passive"))
      (node (ref "R12") (pin "1") (pinfunction "1_1") (pintype "passive"))
    )
    (net (code "38") (name "/HDMI0_CEC") (class "Default")
      (node (ref "J3") (pin "13") (pinfunction "CEC_13") (pintype "passive"))
      (node (ref "M1") (pin "151") (pinfunction "HDMI0_CEC_151") (pintype "input"))
    )
    (net (code "39") (name "/HDMI0_CK_N") (class "Default")
      (node (ref "J3") (pin "12") (pinfunction "TDMS_CLK-_12") (pintype "passive"))
      (node (ref "M1") (pin "190") (pinfunction "HDMI0_CLK_N_190") (pintype "output"))
    )
    (net (code "40") (name "/HDMI0_CK_P") (class "Default")
      (node (ref "J3") (pin "10") (pinfunction "TDMS_CLK+_10") (pintype "passive"))
      (node (ref "M1") (pin "188") (pinfunction "HDMI0_CLK_P_188") (pintype "output"))
    )
    (net (code "41") (name "/HDMI0_D0_N") (class "Default")
      (node (ref "J3") (pin "9") (pinfunction "TDMS_DATA0-_9") (pintype "passive"))
      (node (ref "M1") (pin "184") (pinfunction "HDMI0_TX0_N_184") (pintype "output"))
    )
    (net (code "42") (name "/HDMI0_D0_P") (class "Default")
      (node (ref "J3") (pin "7") (pinfunction "TDMS_DATA0+_7") (pintype "passive"))
      (node (ref "M1") (pin "182") (pinfunction "HDMI0_TX0_P_182") (pintype "output"))
    )
    (net (code "43") (name "/HDMI0_D1_N") (class "Default")
      (node (ref "J3") (pin "6") (pinfunction "TDMS_DATA1-_6") (pintype "passive"))
      (node (ref "M1") (pin "178") (pinfunction "HDMI0_TX1_N_178") (pintype "output"))
    )
    (net (code "44") (name "/HDMI0_D1_P") (class "Default")
      (node (ref "J3") (pin "4") (pinfunction "TDMS_DATA1+_4") (pintype "passive"))
      (node (ref "M1") (pin "176") (pinfunction "HDMI0_TX1_P_176") (pintype "output"))
    )
    (net (code "45") (name "/HDMI0_D2_N") (class "Default")
      (node (ref "J3") (pin "3") (pinfunction "TDMS_DATA2-_3") (pintype "passive"))
      (node (ref "M1") (pin "172") (pinfunction "HDMI0_TX2_N_172") (pintype "output"))
    )
    (net (code "46") (name "/HDMI0_D2_P") (class "Default")
      (node (ref "J3") (pin "1") (pinfunction "TDMS_DATA2+_1") (pintype "passive"))
      (node (ref "M1") (pin "170") (pinfunction "HDMI0_TX2_P_170") (pintype "output"))
    )
    (net (code "47") (name "/HDMI0_HOTPLUG") (class "Default")
      (node (ref "J3") (pin "19") (pinfunction "HOTPLUG_DET_19") (pintype "passive"))
      (node (ref "M1") (pin "153") (pinfunction "HDMI0_HOTPLUG_153") (pintype "input"))
    )
    (net (code "48") (name "/HDMI0_SCL") (class "Default")
      (node (ref "J3") (pin "15") (pinfunction "DDC_SCL_15") (pintype "passive"))
      (node (ref "M1") (pin "200") (pinfunction "HDMI0_SCL_200") (pintype "bidirectional"))
    )
    (net (code "49") (name "/HDMI0_SDA") (class "Default")
      (node (ref "J3") (pin "16") (pinfunction "DDC_SDA_16") (pintype "passive"))
      (node (ref "M1") (pin "199") (pinfunction "HDMI0_SDA_199") (pintype "bidirectional"))
    )
    (net (code "50") (name "/HDMI1_CEC") (class "Default")
      (node (ref "J5") (pin "13") (pinfunction "CEC_13") (pintype "passive"))
      (node (ref "M1") (pin "149") (pinfunction "HDMI1_CEC_149") (pintype "input"))
    )
    (net (code "51") (name "/HDMI1_CK_N") (class "Default")
      (node (ref "J5") (pin "12") (pinfunction "TDMS_CLK-_12") (pintype "passive"))
      (node (ref "M1") (pin "166") (pinfunction "HDMI1_CLK_N_166") (pintype "output"))
    )
    (net (code "52") (name "/HDMI1_CK_P") (class "Default")
      (node (ref "J5") (pin "10") (pinfunction "TDMS_CLK+_10") (pintype "passive"))
      (node (ref "M1") (pin "164") (pinfunction "HDMI1_CLK_P_164") (pintype "output"))
    )
    (net (code "53") (name "/HDMI1_D0_N") (class "Default")
      (node (ref "J5") (pin "9") (pinfunction "TDMS_DATA0-_9") (pintype "passive"))
      (node (ref "M1") (pin "160") (pinfunction "HDMI1_TX0_N_160") (pintype "output"))
    )
    (net (code "54") (name "/HDMI1_D0_P") (class "Default")
      (node (ref "J5") (pin "7") (pinfunction "TDMS_DATA0+_7") (pintype "passive"))
      (node (ref "M1") (pin "158") (pinfunction "HDMI1_TX0_P_158") (pintype "output"))
    )
    (net (code "55") (name "/HDMI1_D1_N") (class "Default")
      (node (ref "J5") (pin "6") (pinfunction "TDMS_DATA1-_6") (pintype "passive"))
      (node (ref "M1") (pin "154") (pinfunction "HDMI1_TX1_N_154") (pintype "output"))
    )
    (net (code "56") (name "/HDMI1_D1_P") (class "Default")
      (node (ref "J5") (pin "4") (pinfunction "TDMS_DATA1+_4") (pintype "passive"))
      (node (ref "M1") (pin "152") (pinfunction "HDMI1_TX1_P_152") (pintype "output"))
    )
    (net (code "57") (name "/HDMI1_D2_N") (class "Default")
      (node (ref "J5") (pin "3") (pinfunction "TDMS_DATA2-_3") (pintype "passive"))
      (node (ref "M1") (pin "148") (pinfunction "HDMI1_TX2_N_148") (pintype "output"))
    )
    (net (code "58") (name "/HDMI1_D2_P") (class "Default")
      (node (ref "J5") (pin "1") (pinfunction "TDMS_DATA2+_1") (pintype "passive"))
      (node (ref "M1") (pin "146") (pinfunction "HDMI1_TX2_P_146") (pintype "output"))
    )
    (net (code "59") (name "/HDMI1_HOTPLUG") (class "Default")
      (node (ref "J5") (pin "19") (pinfunction "HOTPLUG_DET_19") (pintype "passive"))
      (node (ref "M1") (pin "143") (pinfunction "HDMI1_HOTPLUG_143") (pintype "input"))
    )
    (net (code "60") (name "/HDMI1_SCL") (class "Default")
      (node (ref "J5") (pin "15") (pinfunction "DDC_SCL_15") (pintype "passive"))
      (node (ref "M1") (pin "145") (pinfunction "HDMI1_SDA_145") (pintype "bidirectional"))
    )
    (net (code "61") (name "/HDMI1_SDA") (class "Default")
      (node (ref "J5") (pin "16") (pinfunction "DDC_SDA_16") (pintype "passive"))
      (node (ref "M1") (pin "147") (pinfunction "HDMI1_SCL_147") (pintype "bidirectional"))
    )
    (net (code "62") (name "/ID_SC") (class "Default")
      (node (ref "JP3") (pin "4") (pintype "passive"))
      (node (ref "M1") (pin "35") (pinfunction "ID_SC_35") (pintype "bidirectional"))
    )
    (net (code "63") (name "/ID_SD") (class "Default")
      (node (ref "JP3") (pin "3") (pintype "passive"))
      (node (ref "M1") (pin "36") (pinfunction "ID_SD_36") (pintype "bidirectional"))
    )
    (net (code "64") (name "/RCT") (class "Default")
      (node (ref "C52") (pin "1") (pinfunction "1_1") (pintype "passive"))
      (node (ref "R29") (pin "1") (pinfunction "1_1") (pintype "passive"))
      (node (ref "R35") (pin "2") (pinfunction "2_2") (pintype "passive"))
      (node (ref "RJ？") (pin "5") (pintype "passive"))
    )
    (net (code "65") (name "/RUN_PG") (class "Default")
      (node (ref "JP4") (pin "12") (pintype "passive"))
      (node (ref "M1") (pin "92") (pinfunction "RUN_PG_92") (pintype "bidirectional"))
      (node (ref "U5") (pin "2") (pinfunction "A_2") (pintype "input"))
    )
    (net (code "66") (name "/RXNNET") (class "Default")
      (node (ref "C53") (pin "2") (pinfunction "2_2") (pintype "passive"))
      (node (ref "RJ？") (pin "6") (pinfunction "RD-_6") (pintype "passive"))
    )
    (net (code "67") (name "/RXPNET") (class "Default")
      (node (ref "C30") (pin "2") (pinfunction "2_2") (pintype "passive"))
      (node (ref "RJ？") (pin "3") (pinfunction "RD+_3") (pintype "passive"))
    )
    (net (code "68") (name "/SCL0") (class "Default")
      (node (ref "M1") (pin "80") (pinfunction "SCL0_80") (pintype "input"))
      (node (ref "R24") (pin "4") (pinfunction "4_4") (pintype "passive"))
      (node (ref "U6") (pin "16") (pinfunction "SCL_16") (pintype "passive"))
      (node (ref "U7") (pin "2") (pinfunction "SCL_2") (pintype "passive"))
    )
    (net (code "69") (name "/SDA0") (class "Default")
      (node (ref "M1") (pin "82") (pinfunction "SDA0_82") (pintype "bidirectional"))
      (node (ref "R24") (pin "3") (pinfunction "3_3") (pintype "passive"))
      (node (ref "U6") (pin "15") (pinfunction "SDA_15") (pintype "passive"))
      (node (ref "U7") (pin "1") (pinfunction "SDA_1") (pintype "passive"))
    )
    (net (code "70") (name "/SD_CLK") (class "Default")
      (node (ref "M1") (pin "57") (pinfunction "SD_CLK_57") (pintype "bidirectional"))
      (node (ref "MicroSD1") (pin "5") (pinfunction "CLK_5") (pintype "passive"))
    )
    (net (code "71") (name "/SD_CMD") (class "Default")
      (node (ref "M1") (pin "62") (pinfunction "SD_CMD_62") (pintype "input"))
      (node (ref "MicroSD1") (pin "3") (pinfunction "CMD_3") (pintype "passive"))
    )
    (net (code "72") (name "/SD_DATA0") (class "Default")
      (node (ref "M1") (pin "63") (pinfunction "SD_DAT0_63") (pintype "bidirectional"))
      (node (ref "MicroSD1") (pin "7") (pinfunction "D0_7") (pintype "passive"))
    )
    (net (code "73") (name "/SD_DATA1") (class "Default")
      (node (ref "M1") (pin "67") (pinfunction "SD_DAT1_67") (pintype "bidirectional"))
      (node (ref "MicroSD1") (pin "8") (pinfunction "D1_8") (pintype "passive"))
    )
    (net (code "74") (name "/SD_DATA2") (class "Default")
      (node (ref "M1") (pin "69") (pinfunction "SD_DAT2_69") (pintype "bidirectional"))
      (node (ref "MicroSD1") (pin "1") (pinfunction "D2_1") (pintype "passive"))
    )
    (net (code "75") (name "/SD_DATA3") (class "Default")
      (node (ref "M1") (pin "61") (pinfunction "SD_DAT3_61") (pintype "bidirectional"))
      (node (ref "MicroSD1") (pin "2") (pinfunction "D3_2") (pintype "passive"))
    )
    (net (code "76") (name "/SD_PWR_ON") (class "Default")
      (node (ref "M1") (pin "75") (pinfunction "SD_PWR_ON_75") (pintype "output"))
    )
    (net (code "77") (name "/SYNC_IN") (class "Default")
      (node (ref "M1") (pin "16") (pinfunction "ETHERNET_SYNC_IN_16") (pintype "input"))
    )
    (net (code "78") (name "/SYNC_OUT") (class "Default")
      (node (ref "M1") (pin "18") (pinfunction "ETHERNET_SYNC_OUT_18") (pintype "output"))
    )
    (net (code "79") (name "/TCT") (class "Default")
      (node (ref "C54") (pin "1") (pinfunction "1_1") (pintype "passive"))
      (node (ref "R34") (pin "2") (pinfunction "2_2") (pintype "passive"))
      (node (ref "RJ？") (pin "4") (pintype "passive"))
    )
    (net (code "80") (name "/TRD0_N") (class "Default")
      (node (ref "IC1") (pin "2") (pinfunction "IN2_2") (pintype "input"))
      (node (ref "IC1") (pin "9") (pinfunction "NC_9") (pintype "output"))
      (node (ref "M1") (pin "10") (pinfunction "ETHERNET_PAIR0_N_10") (pintype "bidirectional"))
      (node (ref "R33") (pin "2") (pinfunction "2_2") (pintype "passive"))
      (node (ref "RJ？") (pin "2") (pinfunction "TD-_2") (pintype "passive"))
    )
    (net (code "81") (name "/TRD0_P") (class "Default")
      (node (ref "IC1") (pin "1") (pinfunction "IN1_1") (pintype "input"))
      (node (ref "IC1") (pin "10") (pinfunction "NC_10") (pintype "output"))
      (node (ref "M1") (pin "12") (pinfunction "ETHERNET_PAIR0_P_12") (pintype "bidirectional"))
      (node (ref "R32") (pin "1") (pinfunction "1_1") (pintype "passive"))
      (node (ref "RJ？") (pin "1") (pinfunction "TD+_1") (pintype "passive"))
    )
    (net (code "82") (name "/TRD1_N") (class "Default")
      (node (ref "C53") (pin "1") (pinfunction "1_1") (pintype "passive"))
      (node (ref "IC1") (pin "5") (pinfunction "IN5_5") (pintype "input"))
      (node (ref "IC1") (pin "6") (pinfunction "NC_6") (pintype "output"))
      (node (ref "M1") (pin "6") (pinfunction "ETHERNET_PAIR1_N_6") (pintype "bidirectional"))
      (node (ref "R35") (pin "1") (pinfunction "1_1") (pintype "passive"))
    )
    (net (code "83") (name "/TRD1_P") (class "Default")
      (node (ref "C30") (pin "1") (pinfunction "1_1") (pintype "passive"))
      (node (ref "IC1") (pin "4") (pinfunction "IN4_4") (pintype "input"))
      (node (ref "IC1") (pin "7") (pinfunction "NC_7") (pintype "output"))
      (node (ref "M1") (pin "4") (pinfunction "ETHERNET_PAIR1_P_4") (pintype "bidirectional"))
      (node (ref "R29") (pin "2") (pinfunction "2_2") (pintype "passive"))
    )
    (net (code "84") (name "/TRD2_N") (class "Default")
      (node (ref "M1") (pin "9") (pinfunction "ETHERNET_PAIR2_N_9") (pintype "bidirectional"))
    )
    (net (code "85") (name "/TRD2_P") (class "Default")
      (node (ref "M1") (pin "11") (pinfunction "ETHERNET_PAIR2_P_11") (pintype "bidirectional"))
    )
    (net (code "86") (name "/TRD3_N") (class "Default")
      (node (ref "M1") (pin "5") (pinfunction "ETHERNET_PAIR3_N_5") (pintype "bidirectional"))
    )
    (net (code "87") (name "/TRD3_P") (class "Default")
      (node (ref "M1") (pin "3") (pinfunction "ETHERNET_PAIR3_P_3") (pintype "bidirectional"))
    )
    (net (code "88") (name "/TV_OUT") (class "Default")
      (node (ref "M1") (pin "111") (pinfunction "VDAC_COMP_111") (pintype "output"))
    )
    (net (code "89") (name "/USB1_D_N") (class "Default")
      (node (ref "J1") (pin "2") (pinfunction "D1-_2") (pintype "passive"))
      (node (ref "U1") (pin "1") (pinfunction "DM1_1") (pintype "bidirectional"))
    )
    (net (code "90") (name "/USB1_D_P") (class "Default")
      (node (ref "J1") (pin "3") (pinfunction "D1+_3") (pintype "passive"))
      (node (ref "U1") (pin "2") (pinfunction "DP1_2") (pintype "bidirectional"))
    )
    (net (code "91") (name "/USB2_D_N") (class "Default")
      (node (ref "J1") (pin "6") (pinfunction "D2-_6") (pintype "passive"))
      (node (ref "U1") (pin "3") (pinfunction "DM2_3") (pintype "bidirectional"))
    )
    (net (code "92") (name "/USB2_D_P") (class "Default")
      (node (ref "J1") (pin "7") (pinfunction "D2+_7") (pintype "passive"))
      (node (ref "U1") (pin "4") (pinfunction "DP2_4") (pintype "bidirectional"))
    )
    (net (code "93") (name "/USB2_N") (class "Default")
      (node (ref "M1") (pin "103") (pinfunction "USB_N_103") (pintype "bidirectional"))
      (node (ref "U1") (pin "30") (pinfunction "DM-UP_30") (pintype "bidirectional"))
    )
    (net (code "94") (name "/USB2_P") (class "Default")
      (node (ref "M1") (pin "105") (pinfunction "USB_P_105") (pintype "bidirectional"))
      (node (ref "U1") (pin "31") (pinfunction "DP-UP_31") (pintype "bidirectional"))
    )
    (net (code "95") (name "/USB3_D_N") (class "Default")
      (node (ref "J2") (pin "6") (pinfunction "D2-_6") (pintype "passive"))
      (node (ref "U1") (pin "6") (pinfunction "DM3_6") (pintype "bidirectional"))
    )
    (net (code "96") (name "/USB3_D_P") (class "Default")
      (node (ref "J2") (pin "7") (pinfunction "D2+_7") (pintype "passive"))
      (node (ref "U1") (pin "7") (pinfunction "DP3_7") (pintype "bidirectional"))
    )
    (net (code "97") (name "/USB4_D_N") (class "Default")
      (node (ref "J2") (pin "2") (pinfunction "D1-_2") (pintype "passive"))
      (node (ref "U1") (pin "8") (pinfunction "DM4_8") (pintype "bidirectional"))
    )
    (net (code "98") (name "/USB4_D_P") (class "Default")
      (node (ref "J2") (pin "3") (pinfunction "D1+_3") (pintype "passive"))
      (node (ref "U1") (pin "9") (pinfunction "DP4_9") (pintype "bidirectional"))
    )
    (net (code "99") (name "/USBOTG_ID") (class "Default")
      (node (ref "M1") (pin "101") (pinfunction "USB_OTG_ID_101") (pintype "input"))
      (node (ref "R1") (pin "1") (pinfunction "1_1") (pintype "passive"))
    )
    (net (code "100") (name "/WL_nDis") (class "Default")
      (node (ref "JP4") (pin "7") (pintype "passive"))
      (node (ref "M1") (pin "89") (pinfunction "WL_!DISABLE_89") (pintype "input"))
    )
    (net (code "101") (name "/nEXTRST") (class "Default")
      (node (ref "M1") (pin "100") (pinfunction "~{EXTRST}_100") (pintype "output"))
      (node (ref "U1") (pin "26") (pinfunction "~{RESET}_26") (pintype "bidirectional"))
    )
    (net (code "102") (name "/nOCSS1") (class "Default")
      (node (ref "U1") (pin "13") (pinfunction "OCS1_13") (pintype "bidirectional"))
      (node (ref "U1") (pin "17") (pinfunction "OCS2_17") (pintype "bidirectional"))
      (node (ref "U1") (pin "19") (pinfunction "OCS3_19") (pintype "bidirectional"))
      (node (ref "U1") (pin "21") (pinfunction "OCS4_21") (pintype "bidirectional"))
    )
    (net (code "103") (name "/nPWR_LED") (class "Default")
      (node (ref "M1") (pin "95") (pinfunction "PI_LED_!PWR_95") (pintype "output"))
      (node (ref "U4") (pin "2") (pinfunction "A_2") (pintype "input"))
    )
    (net (code "104") (name "/nRPIBOOT") (class "Default")
      (node (ref "JP4") (pin "2") (pintype "passive"))
      (node (ref "M1") (pin "93") (pinfunction "~{RPIBOOT}_93") (pintype "input"))
    )
    (net (code "105") (name "1.8V_RPI") (class "Default")
      (node (ref "M1") (pin "88") (pinfunction "CM4_1.8V(OUTPUT)_88") (pintype "power_in"))
      (node (ref "M1") (pin "90") (pinfunction "CM4_1.8V(OUTPUT)_90") (pintype "power_in"))
      (node (ref "R12") (pin "2") (pinfunction "2_2") (pintype "passive"))
    )
    (net (code "106") (name "3.3V") (class "Default")
      (node (ref "C32") (pin "1") (pinfunction "1_1") (pintype "passive"))
      (node (ref "C33") (pin "1") (pinfunction "1_1") (pintype "passive"))
      (node (ref "C34") (pin "1") (pinfunction "1_1") (pintype "passive"))
      (node (ref "C35") (pin "1") (pinfunction "1_1") (pintype "passive"))
      (node (ref "C36") (pin "1") (pinfunction "A_1") (pintype "passive"))
      (node (ref "C37") (pin "1") (pinfunction "1_1") (pintype "passive"))
      (node (ref "L2") (pin "2") (pinfunction "2_2") (pintype "passive"))
      (node (ref "LED9") (pin "1") (pinfunction "A_1") (pintype "passive"))
      (node (ref "R19") (pin "2") (pinfunction "2_2") (pintype "passive"))
      (node (ref "TP5") (pin "1") (pinfunction "1_1") (pintype "passive"))
    )
    (net (code "107") (name "3.3V_RPI") (class "Default")
      (node (ref "C10") (pin "1") (pinfunction "1_1") (pintype "passive"))
      (node (ref "C2") (pin "1") (pinfunction "1_1") (pintype "passive"))
      (node (ref "C29") (pin "1") (pinfunction "1_1") (pintype "passive"))
      (node (ref "C4") (pin "1") (pinfunction "1_1") (pintype "passive"))
      (node (ref "C47") (pin "1") (pinfunction "1_1") (pintype "passive"))
      (node (ref "C48") (pin "2") (pinfunction "2_2") (pintype "passive"))
      (node (ref "C49") (pin "1") (pinfunction "1_1") (pintype "passive"))
      (node (ref "C5") (pin "1") (pinfunction "1_1") (pintype "passive"))
      (node (ref "C6") (pin "1") (pinfunction "1_1") (pintype "passive"))
      (node (ref "C7") (pin "1") (pinfunction "1_1") (pintype "passive"))
      (node (ref "C8") (pin "1") (pinfunction "1_1") (pintype "passive"))
      (node (ref "C9") (pin "1") (pinfunction "1_1") (pintype "passive"))
      (node (ref "LED10") (pin "1") (pinfunction "A_1") (pintype "passive"))
      (node (ref "LED7") (pin "1") (pinfunction "A_1") (pintype "passive"))
      (node (ref "M1") (pin "84") (pinfunction "CM4_3.3V(OUTPUT)_84") (pintype "power_in"))
      (node (ref "M1") (pin "86") (pinfunction "CM4_3.3V(OUTPUT)_86") (pintype "power_in"))
      (node (ref "MicroSD1") (pin "4") (pinfunction "VCC_4") (pintype "passive"))
      (node (ref "R11") (pin "2") (pinfunction "2_2") (pintype "passive"))
      (node (ref "R24") (pin "5") (pinfunction "5_5") (pintype "passive"))
      (node (ref "R24") (pin "6") (pinfunction "6_6") (pintype "passive"))
      (node (ref "R24") (pin "7") (pinfunction "7_7") (pintype "passive"))
      (node (ref "R24") (pin "8") (pinfunction "8_8") (pintype "passive"))
      (node (ref "R25") (pin "1") (pinfunction "1_1") (pintype "passive"))
      (node (ref "R26") (pin "2") (pinfunction "2_2") (pintype "passive"))
      (node (ref "R32") (pin "2") (pinfunction "2_2") (pintype "passive"))
      (node (ref "R33") (pin "1") (pinfunction "1_1") (pintype "passive"))
      (node (ref "R34") (pin "1") (pinfunction "1_1") (pintype "passive"))
      (node (ref "RJ？") (pin "12") (pinfunction "LED2+_12") (pintype "passive"))
      (node (ref "RJ？") (pin "9") (pinfunction "LED1+_9") (pintype "passive"))
      (node (ref "U1") (pin "10") (pinfunction "VDDA33_10") (pintype "bidirectional"))
      (node (ref "U1") (pin "15") (pinfunction "VDD33_15") (pintype "bidirectional"))
      (node (ref "U1") (pin "23") (pinfunction "VDD33_23") (pintype "bidirectional"))
      (node (ref "U1") (pin "27") (pinfunction "VBUS_DET_27") (pintype "bidirectional"))
      (node (ref "U1") (pin "29") (pinfunction "VDDA33_29") (pintype "bidirectional"))
      (node (ref "U1") (pin "36") (pinfunction "VDDA33_36") (pintype "bidirectional"))
      (node (ref "U1") (pin "5") (pinfunction "VDDA33_5") (pintype "bidirectional"))
      (node (ref "U4") (pin "5") (pinfunction "VCC_5") (pintype "power_in"))
      (node (ref "U6") (pin "2") (pinfunction "VCC_2") (pintype "passive"))
      (node (ref "U7") (pin "3") (pinfunction "VDD_3") (pintype "passive"))
    )
    (net (code "108") (name "5V") (class "Default")
      (node (ref "C14") (pin "1") (pinfunction "1_1") (pintype "passive"))
      (node (ref "C15") (pin "1") (pinfunction "1_1") (pintype "passive"))
      (node (ref "C16") (pin "1") (pinfunction "1_1") (pintype "passive"))
      (node (ref "C17") (pin "1") (pinfunction "1_1") (pintype "passive"))
      (node (ref "C18") (pin "1") (pinfunction "A_1") (pintype "passive"))
      (node (ref "C19") (pin "1") (pinfunction "1_1") (pintype "passive"))
      (node (ref "C50") (pin "1") (pinfunction "1_1") (pintype "passive"))
      (node (ref "J1") (pin "1") (pinfunction "VUSB1_1") (pintype "passive"))
      (node (ref "J1") (pin "5") (pinfunction "VUSB2_5") (pintype "passive"))
      (node (ref "J2") (pin "1") (pinfunction "VUSB1_1") (pintype "passive"))
      (node (ref "J2") (pin "5") (pinfunction "VUSB2_5") (pintype "passive"))
      (node (ref "J3") (pin "18") (pinfunction "DDC_+5V_18") (pintype "passive"))
      (node (ref "J5") (pin "18") (pinfunction "DDC_+5V_18") (pintype "passive"))
      (node (ref "JP2") (pin "4") (pintype "passive"))
      (node (ref "L1") (pin "2") (pinfunction "2_2") (pintype "passive"))
      (node (ref "LED8") (pin "1") (pinfunction "A_1") (pintype "passive"))
      (node (ref "M1") (pin "77") (pinfunction "+5V(INPUT)_77") (pintype "power_in"))
      (node (ref "M1") (pin "79") (pinfunction "+5V(INPUT)_79") (pintype "power_in"))
      (node (ref "M1") (pin "81") (pinfunction "+5V(INPUT)_81") (pintype "power_in"))
      (node (ref "M1") (pin "83") (pinfunction "+5V(INPUT)_83") (pintype "power_in"))
      (node (ref "M1") (pin "85") (pinfunction "+5V(INPUT)_85") (pintype "power_in"))
      (node (ref "M1") (pin "87") (pinfunction "+5V(INPUT)_87") (pintype "power_in"))
      (node (ref "R10") (pin "2") (pinfunction "2_2") (pintype "passive"))
      (node (ref "R27") (pin "2") (pinfunction "2_2") (pintype "passive"))
      (node (ref "R28") (pin "1") (pinfunction "1_1") (pintype "passive"))
      (node (ref "TP2") (pin "1") (pinfunction "1_1") (pintype "passive"))
      (node (ref "U5") (pin "5") (pinfunction "VCC_5") (pintype "power_in"))
      (node (ref "U8") (pin "5") (pinfunction "VCC_5") (pintype "power_in"))
    )
    (net (code "109") (name "12V") (class "Default")
      (node (ref "C20") (pin "1") (pinfunction "1_1") (pintype "passive"))
      (node (ref "C21") (pin "1") (pinfunction "1_1") (pintype "passive"))
      (node (ref "C22") (pin "1") (pinfunction "1_1") (pintype "passive"))
      (node (ref "C23") (pin "1") (pinfunction "1_1") (pintype "passive"))
      (node (ref "C24") (pin "1") (pinfunction "1_1") (pintype "passive"))
      (node (ref "C25") (pin "1") (pinfunction "1_1") (pintype "passive"))
      (node (ref "C3") (pin "1") (pinfunction "1_1") (pintype "passive"))
      (node (ref "C38") (pin "1") (pinfunction "1_1") (pintype "passive"))
      (node (ref "C39") (pin "1") (pinfunction "1_1") (pintype "passive"))
      (node (ref "C40") (pin "1") (pinfunction "1_1") (pintype "passive"))
      (node (ref "C41") (pin "1") (pinfunction "1_1") (pintype "passive"))
      (node (ref "C42") (pin "1") (pinfunction "1_1") (pintype "passive"))
      (node (ref "C43") (pin "1") (pinfunction "1_1") (pintype "passive"))
      (node (ref "JP2") (pin "1") (pintype "passive"))
      (node (ref "JP6") (pin "2") (pintype "passive"))
      (node (ref "LED2") (pin "1") (pinfunction "A_1") (pintype "passive"))
      (node (ref "Q1") (pin "1-3") (pinfunction "S_1-3") (pintype "passive"))
      (node (ref "TP3") (pin "1") (pinfunction "1_1") (pintype "passive"))
      (node (ref "U2") (pin "2") (pinfunction "VIN_2") (pintype "input"))
      (node (ref "U2") (pin "3") (pinfunction "EN_3") (pintype "bidirectional"))
      (node (ref "U3") (pin "2") (pinfunction "VIN_2") (pintype "input"))
      (node (ref "U3") (pin "3") (pinfunction "EN_3") (pintype "bidirectional"))
      (node (ref "Z1") (pin "2") (pinfunction "K_2") (pintype "passive"))
    )
    (net (code "110") (name "GND") (class "Default")
      (node (ref "Battery1") (pin "2") (pinfunction "-_2") (pintype "passive"))
      (node (ref "C1") (pin "2") (pinfunction "2_2") (pintype "passive"))
      (node (ref "C10") (pin "2") (pinfunction "2_2") (pintype "passive"))
      (node (ref "C11") (pin "2") (pinfunction "2_2") (pintype "passive"))
      (node (ref "C12") (pin "2") (pinfunction "2_2") (pintype "passive"))
      (node (ref "C14") (pin "2") (pinfunction "2_2") (pintype "passive"))
      (node (ref "C15") (pin "2") (pinfunction "2_2") (pintype "passive"))
      (node (ref "C16") (pin "2") (pinfunction "2_2") (pintype "passive"))
      (node (ref "C17") (pin "2") (pinfunction "2_2") (pintype "passive"))
      (node (ref "C18") (pin "2") (pinfunction "K_2") (pintype "passive"))
      (node (ref "C2") (pin "2") (pinfunction "2_2") (pintype "passive"))
      (node (ref "C20") (pin "2") (pinfunction "2_2") (pintype "passive"))
      (node (ref "C21") (pin "2") (pinfunction "2_2") (pintype "passive"))
      (node (ref "C22") (pin "2") (pinfunction "2_2") (pintype "passive"))
      (node (ref "C23") (pin "2") (pinfunction "2_2") (pintype "passive"))
      (node (ref "C24") (pin "2") (pinfunction "2_2") (pintype "passive"))
      (node (ref "C25") (pin "2") (pinfunction "2_2") (pintype "passive"))
      (node (ref "C26") (pin "2") (pinfunction "2_2") (pintype "passive"))
      (node (ref "C27") (pin "2") (pinfunction "2_2") (pintype "passive"))
      (node (ref "C28") (pin "2") (pinfunction "2_2") (pintype "passive"))
      (node (ref "C29") (pin "2") (pinfunction "2_2") (pintype "passive"))
      (node (ref "C3") (pin "2") (pinfunction "2_2") (pintype "passive"))
      (node (ref "C32") (pin "2") (pinfunction "2_2") (pintype "passive"))
      (node (ref "C33") (pin "2") (pinfunction "2_2") (pintype "passive"))
      (node (ref "C34") (pin "2") (pinfunction "2_2") (pintype "passive"))
      (node (ref "C35") (pin "2") (pinfunction "2_2") (pintype "passive"))
      (node (ref "C36") (pin "2") (pinfunction "K_2") (pintype "passive"))
      (node (ref "C38") (pin "2") (pinfunction "2_2") (pintype "passive"))
      (node (ref "C39") (pin "2") (pinfunction "2_2") (pintype "passive"))
      (node (ref "C4") (pin "2") (pinfunction "2_2") (pintype "passive"))
      (node (ref "C40") (pin "2") (pinfunction "2_2") (pintype "passive"))
      (node (ref "C41") (pin "2") (pinfunction "2_2") (pintype "passive"))
      (node (ref "C42") (pin "2") (pinfunction "2_2") (pintype "passive"))
      (node (ref "C43") (pin "2") (pinfunction "2_2") (pintype "passive"))
      (node (ref "C44") (pin "2") (pinfunction "2_2") (pintype "passive"))
      (node (ref "C45") (pin "2") (pinfunction "2_2") (pintype "passive"))
      (node (ref "C46") (pin "2") (pinfunction "2_2") (pintype "passive"))
      (node (ref "C47") (pin "2") (pinfunction "2_2") (pintype "passive"))
      (node (ref "C48") (pin "1") (pinfunction "1_1") (pintype "passive"))
      (node (ref "C49") (pin "2") (pinfunction "2_2") (pintype "passive"))
      (node (ref "C5") (pin "2") (pinfunction "2_2") (pintype "passive"))
      (node (ref "C50") (pin "2") (pinfunction "2_2") (pintype "passive"))
      (node (ref "C52") (pin "2") (pinfunction "2_2") (pintype "passive"))
      (node (ref "C54") (pin "2") (pinfunction "2_2") (pintype "passive"))
      (node (ref "C6") (pin "2") (pinfunction "2_2") (pintype "passive"))
      (node (ref "C7") (pin "2") (pinfunction "2_2") (pintype "passive"))
      (node (ref "C8") (pin "2") (pinfunction "2_2") (pintype "passive"))
      (node (ref "C9") (pin "2") (pinfunction "2_2") (pintype "passive"))
      (node (ref "IC1") (pin "3_8") (pinfunction "GND_3_8") (pintype "power_in"))
      (node (ref "J1") (pin "4") (pinfunction "GND1_4") (pintype "passive"))
      (node (ref "J1") (pin "8") (pinfunction "GND2_8") (pintype "passive"))
      (node (ref "J1") (pin "S1") (pinfunction "SHIELD_S1") (pintype "passive"))
      (node (ref "J1") (pin "S2") (pinfunction "SHIELD_S2") (pintype "passive"))
      (node (ref "J1") (pin "S3") (pinfunction "SHIELD_S3") (pintype "passive"))
      (node (ref "J1") (pin "S4") (pinfunction "SHIELD_S4") (pintype "passive"))
      (node (ref "J2") (pin "4") (pinfunction "GND1_4") (pintype "passive"))
      (node (ref "J2") (pin "8") (pinfunction "GND2_8") (pintype "passive"))
      (node (ref "J2") (pin "S1") (pinfunction "SHIELD_S1") (pintype "passive"))
      (node (ref "J2") (pin "S2") (pinfunction "SHIELD_S2") (pintype "passive"))
      (node (ref "J2") (pin "S3") (pinfunction "SHIELD_S3") (pintype "passive"))
      (node (ref "J2") (pin "S4") (pinfunction "SHIELD_S4") (pintype "passive"))
      (node (ref "J3") (pin "11") (pinfunction "TDMS_CLK_SH_11") (pintype "passive"))
      (node (ref "J3") (pin "17") (pinfunction "DDC_CEC_GND_17") (pintype "passive"))
      (node (ref "J3") (pin "2") (pinfunction "TDMS_SHLD2_2") (pintype "passive"))
      (node (ref "J3") (pin "20") (pinfunction "SHIELD_20") (pintype "passive"))
      (node (ref "J3") (pin "21") (pinfunction "SHIELD_21") (pintype "passive"))
      (node (ref "J3") (pin "22") (pinfunction "SHIELD_22") (pintype "passive"))
      (node (ref "J3") (pin "23") (pinfunction "SHIELD_23") (pintype "passive"))
      (node (ref "J3") (pin "5") (pinfunction "TDMS_SHLD1_5") (pintype "passive"))
      (node (ref "J3") (pin "8") (pinfunction "TDMS_SHLD0_8") (pintype "passive"))
      (node (ref "J5") (pin "11") (pinfunction "TDMS_CLK_SH_11") (pintype "passive"))
      (node (ref "J5") (pin "17") (pinfunction "DDC_CEC_GND_17") (pintype "passive"))
      (node (ref "J5") (pin "2") (pinfunction "TDMS_SHLD2_2") (pintype "passive"))
      (node (ref "J5") (pin "20") (pinfunction "SHIELD_20") (pintype "passive"))
      (node (ref "J5") (pin "21") (pinfunction "SHIELD_21") (pintype "passive"))
      (node (ref "J5") (pin "22") (pinfunction "SHIELD_22") (pintype "passive"))
      (node (ref "J5") (pin "23") (pinfunction "SHIELD_23") (pintype "passive"))
      (node (ref "J5") (pin "5") (pinfunction "TDMS_SHLD1_5") (pintype "passive"))
      (node (ref "J5") (pin "8") (pinfunction "TDMS_SHLD0_8") (pintype "passive"))
      (node (ref "JP1") (pin "1") (pintype "passive"))
      (node (ref "JP2") (pin "2") (pintype "passive"))
      (node (ref "JP2") (pin "3") (pintype "passive"))
      (node (ref "JP3") (pin "1") (pintype "passive"))
      (node (ref "JP3") (pin "10") (pintype "passive"))
      (node (ref "JP3") (pin "15") (pintype "passive"))
      (node (ref "JP3") (pin "6") (pintype "passive"))
      (node (ref "JP4") (pin "1") (pintype "passive"))
      (node (ref "JP4") (pin "10") (pintype "passive"))
      (node (ref "JP4") (pin "3") (pintype "passive"))
      (node (ref "JP4") (pin "9") (pintype "passive"))
      (node (ref "JP6") (pin "1") (pintype "passive"))
      (node (ref "M1") (pin "1") (pinfunction "GND_1") (pintype "power_in"))
      (node (ref "M1") (pin "107") (pinfunction "GND_107") (pintype "power_in"))
      (node (ref "M1") (pin "108") (pinfunction "GND_108") (pintype "power_in"))
      (node (ref "M1") (pin "113") (pinfunction "GND_113") (pintype "power_in"))
      (node (ref "M1") (pin "114") (pinfunction "GND_114") (pintype "power_in"))
      (node (ref "M1") (pin "119") (pinfunction "GND_119") (pintype "power_in"))
      (node (ref "M1") (pin "120") (pinfunction "GND_120") (pintype "power_in"))
      (node (ref "M1") (pin "125") (pinfunction "GND_125") (pintype "power_in"))
      (node (ref "M1") (pin "126") (pinfunction "GND_126") (pintype "power_in"))
      (node (ref "M1") (pin "13") (pinfunction "GND_13") (pintype "power_in"))
      (node (ref "M1") (pin "131") (pinfunction "GND_131") (pintype "power_in"))
      (node (ref "M1") (pin "132") (pinfunction "GND_132") (pintype "power_in"))
      (node (ref "M1") (pin "137") (pinfunction "GND_137") (pintype "power_in"))
      (node (ref "M1") (pin "138") (pinfunction "GND_138") (pintype "power_in"))
      (node (ref "M1") (pin "14") (pinfunction "GND_14") (pintype "power_in"))
      (node (ref "M1") (pin "144") (pinfunction "GND_144") (pintype "power_in"))
      (node (ref "M1") (pin "150") (pinfunction "GND_150") (pintype "power_in"))
      (node (ref "M1") (pin "155") (pinfunction "GND_155") (pintype "power_in"))
      (node (ref "M1") (pin "156") (pinfunction "GND_156") (pintype "power_in"))
      (node (ref "M1") (pin "161") (pinfunction "GND_161") (pintype "power_in"))
      (node (ref "M1") (pin "162") (pinfunction "GND_162") (pintype "power_in"))
      (node (ref "M1") (pin "167") (pinfunction "GND_167") (pintype "power_in"))
      (node (ref "M1") (pin "168") (pinfunction "GND_168") (pintype "power_in"))
      (node (ref "M1") (pin "173") (pinfunction "GND_173") (pintype "power_in"))
      (node (ref "M1") (pin "174") (pinfunction "GND_174") (pintype "power_in"))
      (node (ref "M1") (pin "179") (pinfunction "GND_179") (pintype "power_in"))
      (node (ref "M1") (pin "180") (pinfunction "GND_180") (pintype "power_in"))
      (node (ref "M1") (pin "185") (pinfunction "GND_185") (pintype "power_in"))
      (node (ref "M1") (pin "186") (pinfunction "GND_186") (pintype "power_in"))
      (node (ref "M1") (pin "191") (pinfunction "GND_191") (pintype "power_in"))
      (node (ref "M1") (pin "192") (pinfunction "GND_192") (pintype "power_in"))
      (node (ref "M1") (pin "197") (pinfunction "GND_197") (pintype "power_in"))
      (node (ref "M1") (pin "198") (pinfunction "GND_198") (pintype "power_in"))
      (node (ref "M1") (pin "2") (pinfunction "GND_2") (pintype "power_in"))
      (node (ref "M1") (pin "22") (pinfunction "GND_22") (pintype "power_in"))
      (node (ref "M1") (pin "23") (pinfunction "GND_23") (pintype "power_in"))
      (node (ref "M1") (pin "32") (pinfunction "GND_32") (pintype "power_in"))
      (node (ref "M1") (pin "33") (pinfunction "GND_33") (pintype "power_in"))
      (node (ref "M1") (pin "42") (pinfunction "GND_42") (pintype "power_in"))
      (node (ref "M1") (pin "43") (pinfunction "GND_43") (pintype "power_in"))
      (node (ref "M1") (pin "52") (pinfunction "GND_52") (pintype "power_in"))
      (node (ref "M1") (pin "53") (pinfunction "GND_53") (pintype "power_in"))
      (node (ref "M1") (pin "59") (pinfunction "GND_59") (pintype "power_in"))
      (node (ref "M1") (pin "60") (pinfunction "GND_60") (pintype "power_in"))
      (node (ref "M1") (pin "65") (pinfunction "GND_65") (pintype "power_in"))
      (node (ref "M1") (pin "66") (pinfunction "GND_66") (pintype "power_in"))
      (node (ref "M1") (pin "7") (pinfunction "GND_7") (pintype "power_in"))
      (node (ref "M1") (pin "71") (pinfunction "GND_71") (pintype "power_in"))
      (node (ref "M1") (pin "74") (pinfunction "GND_74") (pintype "power_in"))
      (node (ref "M1") (pin "8") (pinfunction "GND_8") (pintype "power_in"))
      (node (ref "M1") (pin "98") (pinfunction "GND_98") (pintype "power_in"))
      (node (ref "MicroSD1") (pin "6") (pinfunction "GND_6") (pintype "passive"))
      (node (ref "R1") (pin "2") (pinfunction "2_2") (pintype "passive"))
      (node (ref "R14") (pin "1") (pinfunction "1_1") (pintype "passive"))
      (node (ref "R17") (pin "2") (pinfunction "2_2") (pintype "passive"))
      (node (ref "R2") (pin "1") (pinfunction "1_1") (pintype "passive"))
      (node (ref "R20") (pin "1") (pinfunction "1_1") (pintype "passive"))
      (node (ref "R21") (pin "1") (pinfunction "1_1") (pintype "passive"))
      (node (ref "R23") (pin "1") (pinfunction "1_1") (pintype "passive"))
      (node (ref "R3") (pin "2") (pinfunction "2_2") (pintype "passive"))
      (node (ref "R4") (pin "1") (pinfunction "1_1") (pintype "passive"))
      (node (ref "R5") (pin "1") (pinfunction "1_1") (pintype "passive"))
      (node (ref "R7") (pin "1") (pinfunction "1_1") (pintype "passive"))
      (node (ref "R9") (pin "2") (pinfunction "2_2") (pintype "passive"))
      (node (ref "RJ？") (pin "0") (pinfunction "SHIELD_0") (pintype "passive"))
      (node (ref "RJ？") (pin "8") (pinfunction "CHS/GND_8") (pintype "passive"))
      (node (ref "RU1") (pin "1") (pinfunction "1_1") (pintype "passive"))
      (node (ref "TP4") (pin "1") (pinfunction "1_1") (pintype "passive"))
      (node (ref "U1") (pin "37") (pinfunction "VSS_37") (pintype "bidirectional"))
      (node (ref "U2") (pin "7") (pinfunction "GND_7") (pintype "power_in"))
      (node (ref "U2") (pin "9") (pinfunction "EP_9") (pintype "bidirectional"))
      (node (ref "U3") (pin "7") (pinfunction "GND_7") (pintype "power_in"))
      (node (ref "U3") (pin "9") (pinfunction "EP_9") (pintype "bidirectional"))
      (node (ref "U4") (pin "3") (pinfunction "GND_3") (pintype "power_in"))
      (node (ref "U5") (pin "3") (pinfunction "GND_3") (pintype "power_in"))
      (node (ref "U6") (pin "13") (pinfunction "GND_13") (pintype "passive"))
      (node (ref "U7") (pin "4") (pinfunction "GND_4") (pintype "passive"))
      (node (ref "U8") (pin "3") (pinfunction "GND_3") (pintype "power_in"))
    )
    (net (code "111") (name "Net-(Battery1-+)") (class "Default")
      (node (ref "Battery1") (pin "1") (pinfunction "+_1") (pintype "passive"))
      (node (ref "D1") (pin "2") (pinfunction "K_2") (pintype "passive"))
      (node (ref "U6") (pin "14") (pinfunction "VBAT_14") (pintype "passive"))
    )
    (net (code "112") (name "Net-(C13-Pad2)") (class "Default")
      (node (ref "C13") (pin "2") (pinfunction "2_2") (pintype "passive"))
      (node (ref "R8") (pin "2") (pinfunction "2_2") (pintype "passive"))
    )
    (net (code "113") (name "Net-(C28-Pad1)") (class "Default")
      (node (ref "C28") (pin "1") (pinfunction "1_1") (pintype "passive"))
      (node (ref "R13") (pin "1") (pinfunction "1_1") (pintype "passive"))
    )
    (net (code "114") (name "Net-(C31-Pad2)") (class "Default")
      (node (ref "C31") (pin "2") (pinfunction "2_2") (pintype "passive"))
      (node (ref "R16") (pin "2") (pinfunction "2_2") (pintype "passive"))
    )
    (net (code "115") (name "Net-(C46-Pad1)") (class "Default")
      (node (ref "C46") (pin "1") (pinfunction "1_1") (pintype "passive"))
      (node (ref "R22") (pin "1") (pinfunction "1_1") (pintype "passive"))
    )
    (net (code "116") (name "Net-(D1-A)") (class "Default")
      (node (ref "D1") (pin "1") (pinfunction "A_1") (pintype "passive"))
      (node (ref "R25") (pin "2") (pinfunction "2_2") (pintype "passive"))
    )
    (net (code "117") (name "Net-(H1-PadP)") (class "Default")
      (node (ref "H1") (pin "P") (pinfunction "P_P") (pintype "passive"))
      (node (ref "H2") (pin "P") (pinfunction "P_P") (pintype "passive"))
      (node (ref "H3") (pin "P") (pinfunction "P_P") (pintype "passive"))
      (node (ref "H4") (pin "P") (pinfunction "P_P") (pintype "passive"))
    )
    (net (code "118") (name "Net-(LED2-K)") (class "Default")
      (node (ref "LED2") (pin "2") (pinfunction "K_2") (pintype "passive"))
      (node (ref "R3") (pin "1") (pinfunction "1_1") (pintype "passive"))
    )
    (net (code "119") (name "Net-(LED7-K)") (class "Default")
      (node (ref "LED7") (pin "2") (pinfunction "K_2") (pintype "passive"))
      (node (ref "R6") (pin "1") (pinfunction "1_1") (pintype "passive"))
    )
    (net (code "120") (name "Net-(LED8-K)") (class "Default")
      (node (ref "LED8") (pin "2") (pinfunction "K_2") (pintype "passive"))
      (node (ref "R9") (pin "1") (pinfunction "1_1") (pintype "passive"))
    )
    (net (code "121") (name "Net-(LED9-K)") (class "Default")
      (node (ref "LED9") (pin "2") (pinfunction "K_2") (pintype "passive"))
      (node (ref "R17") (pin "1") (pinfunction "1_1") (pintype "passive"))
    )
    (net (code "122") (name "Net-(LED10-K)") (class "Default")
      (node (ref "LED10") (pin "2") (pinfunction "K_2") (pintype "passive"))
      (node (ref "R18") (pin "1") (pinfunction "1_1") (pintype "passive"))
    )
    (net (code "123") (name "Net-(M1B-PI_!LED!_ACTIVITY)") (class "Default")
      (node (ref "M1") (pin "21") (pinfunction "PI_!LED!_ACTIVITY_21") (pintype "bidirectional"))
      (node (ref "R6") (pin "2") (pinfunction "2_2") (pintype "passive"))
    )
    (net (code "124") (name "Net-(Q1-D)") (class "Default")
      (node (ref "C1") (pin "1") (pinfunction "1_1") (pintype "passive"))
      (node (ref "JP1") (pin "2") (pintype "passive"))
      (node (ref "Q1") (pin "5-8") (pinfunction "D_5-8") (pintype "passive"))
      (node (ref "RU1") (pin "2") (pinfunction "2_2") (pintype "passive"))
    )
    (net (code "125") (name "Net-(Q1-G)") (class "Default")
      (node (ref "Q1") (pin "4") (pinfunction "G_4") (pintype "passive"))
      (node (ref "R4") (pin "2") (pinfunction "2_2") (pintype "passive"))
      (node (ref "Z1") (pin "1") (pinfunction "A_1") (pintype "passive"))
    )
    (net (code "126") (name "Net-(RJ？-LED1-)") (class "Default")
      (node (ref "R30") (pin "1") (pinfunction "1_1") (pintype "passive"))
      (node (ref "RJ？") (pin "10") (pinfunction "LED1-_10") (pintype "passive"))
    )
    (net (code "127") (name "Net-(RJ？-LED2-)") (class "Default")
      (node (ref "R31") (pin "1") (pinfunction "1_1") (pintype "passive"))
      (node (ref "RJ？") (pin "11") (pinfunction "LED2-_11") (pintype "passive"))
    )
    (net (code "128") (name "Net-(U1-CFG_SEL1)") (class "Default")
      (node (ref "R21") (pin "2") (pinfunction "2_2") (pintype "passive"))
      (node (ref "U1") (pin "25") (pinfunction "CFG_SEL1_25") (pintype "bidirectional"))
    )
    (net (code "129") (name "Net-(U1-RBIAS)") (class "Default")
      (node (ref "R7") (pin "2") (pinfunction "2_2") (pintype "passive"))
      (node (ref "U1") (pin "35") (pinfunction "RBIAS_35") (pintype "bidirectional"))
    )
    (net (code "130") (name "Net-(U1-SMBCLK)") (class "Default")
      (node (ref "R2") (pin "2") (pinfunction "2_2") (pintype "passive"))
      (node (ref "U1") (pin "24") (pinfunction "SMBCLK_24") (pintype "bidirectional"))
    )
    (net (code "131") (name "Net-(U1-SMBDATA)") (class "Default")
      (node (ref "R5") (pin "2") (pinfunction "2_2") (pintype "passive"))
      (node (ref "U1") (pin "22") (pinfunction "SMBDATA_22") (pintype "bidirectional"))
    )
    (net (code "132") (name "Net-(U1-SUSP_IND)") (class "Default")
      (node (ref "R20") (pin "2") (pinfunction "2_2") (pintype "passive"))
      (node (ref "U1") (pin "28") (pinfunction "SUSP_IND_28") (pintype "bidirectional"))
    )
    (net (code "133") (name "Net-(U1-XTAL1)") (class "Default")
      (node (ref "C11") (pin "1") (pinfunction "1_1") (pintype "passive"))
      (node (ref "U1") (pin "32") (pinfunction "XTAL1_32") (pintype "bidirectional"))
      (node (ref "X1") (pin "2") (pinfunction "3_2") (pintype "passive"))
    )
    (net (code "134") (name "Net-(U1-XTAL2)") (class "Default")
      (node (ref "C12") (pin "1") (pinfunction "1_1") (pintype "passive"))
      (node (ref "U1") (pin "33") (pinfunction "XTAL2_33") (pintype "bidirectional"))
      (node (ref "X1") (pin "1") (pinfunction "1_1") (pintype "passive"))
    )
    (net (code "135") (name "Net-(U2-BST)") (class "Default")
      (node (ref "C13") (pin "1") (pinfunction "1_1") (pintype "passive"))
      (node (ref "U2") (pin "1") (pinfunction "BST_1") (pintype "bidirectional"))
    )
    (net (code "136") (name "Net-(U2-COMP)") (class "Default")
      (node (ref "C27") (pin "1") (pinfunction "1_1") (pintype "passive"))
      (node (ref "R13") (pin "2") (pinfunction "2_2") (pintype "passive"))
      (node (ref "U2") (pin "6") (pinfunction "COMP_6") (pintype "bidirectional"))
    )
    (net (code "137") (name "Net-(U2-FB)") (class "Default")
      (node (ref "C19") (pin "2") (pinfunction "2_2") (pintype "passive"))
      (node (ref "R10") (pin "1") (pinfunction "1_1") (pintype "passive"))
      (node (ref "R14") (pin "2") (pinfunction "2_2") (pintype "passive"))
      (node (ref "U2") (pin "5") (pinfunction "FB_5") (pintype "bidirectional"))
    )
    (net (code "138") (name "Net-(U2-SS)") (class "Default")
      (node (ref "C26") (pin "1") (pinfunction "1_1") (pintype "passive"))
      (node (ref "U2") (pin "4") (pinfunction "SS_4") (pintype "bidirectional"))
    )
    (net (code "139") (name "Net-(U2-SW)") (class "Default")
      (node (ref "L1") (pin "1") (pinfunction "1_1") (pintype "passive"))
      (node (ref "R8") (pin "1") (pinfunction "1_1") (pintype "passive"))
      (node (ref "U2") (pin "8") (pinfunction "SW_8") (pintype "bidirectional"))
    )
    (net (code "140") (name "Net-(U3-BST)") (class "Default")
      (node (ref "C31") (pin "1") (pinfunction "1_1") (pintype "passive"))
      (node (ref "U3") (pin "1") (pinfunction "BST_1") (pintype "bidirectional"))
    )
    (net (code "141") (name "Net-(U3-COMP)") (class "Default")
      (node (ref "C45") (pin "1") (pinfunction "1_1") (pintype "passive"))
      (node (ref "R22") (pin "2") (pinfunction "2_2") (pintype "passive"))
      (node (ref "U3") (pin "6") (pinfunction "COMP_6") (pintype "bidirectional"))
    )
    (net (code "142") (name "Net-(U3-FB)") (class "Default")
      (node (ref "C37") (pin "2") (pinfunction "2_2") (pintype "passive"))
      (node (ref "R19") (pin "1") (pinfunction "1_1") (pintype "passive"))
      (node (ref "R23") (pin "2") (pinfunction "2_2") (pintype "passive"))
      (node (ref "U3") (pin "5") (pinfunction "FB_5") (pintype "bidirectional"))
    )
    (net (code "143") (name "Net-(U3-SS)") (class "Default")
      (node (ref "C44") (pin "1") (pinfunction "1_1") (pintype "passive"))
      (node (ref "U3") (pin "4") (pinfunction "SS_4") (pintype "bidirectional"))
    )
    (net (code "144") (name "Net-(U3-SW)") (class "Default")
      (node (ref "L2") (pin "1") (pinfunction "1_1") (pintype "passive"))
      (node (ref "R16") (pin "1") (pinfunction "1_1") (pintype "passive"))
      (node (ref "U3") (pin "8") (pinfunction "SW_8") (pintype "bidirectional"))
    )
    (net (code "145") (name "Net-(U4-Y)") (class "Default")
      (node (ref "R18") (pin "2") (pinfunction "2_2") (pintype "passive"))
      (node (ref "U4") (pin "4") (pinfunction "Y_4") (pintype "output"))
    )
    (net (code "146") (name "Net-(U5-Y)") (class "Default")
      (node (ref "JP4") (pin "5") (pintype "passive"))
      (node (ref "U5") (pin "4") (pinfunction "Y_4") (pintype "output"))
    )
    (net (code "147") (name "Net-(U7-PWM)") (class "Default")
      (node (ref "JP6") (pin "4") (pintype "passive"))
      (node (ref "U7") (pin "5") (pinfunction "PWM_5") (pintype "passive"))
    )
    (net (code "148") (name "Net-(U7-TACH)") (class "Default")
      (node (ref "JP6") (pin "3") (pintype "passive"))
      (node (ref "R26") (pin "1") (pinfunction "1_1") (pintype "passive"))
      (node (ref "U7") (pin "6") (pinfunction "TACH_6") (pintype "passive"))
    )
    (net (code "149") (name "Net-(U8-A)") (class "Default")
      (node (ref "C51") (pin "1") (pinfunction "1_1") (pintype "passive"))
      (node (ref "R28") (pin "2") (pinfunction "2_2") (pintype "passive"))
      (node (ref "U8") (pin "2") (pinfunction "A_2") (pintype "input"))
    )
    (net (code "150") (name "unconnected-(J3-RESERVED-Pad14)") (class "Default")
      (node (ref "J3") (pin "14") (pinfunction "RESERVED_14") (pintype "passive+no_connect"))
    )
    (net (code "151") (name "unconnected-(J5-RESERVED-Pad14)") (class "Default")
      (node (ref "J5") (pin "14") (pinfunction "RESERVED_14") (pintype "passive+no_connect"))
    )
    (net (code "152") (name "unconnected-(M1A-CAM0_C_N-Pad140)") (class "Default")
      (node (ref "M1") (pin "140") (pinfunction "CAM0_C_N_140") (pintype "input+no_connect"))
    )
    (net (code "153") (name "unconnected-(M1A-CAM0_C_P-Pad142)") (class "Default")
      (node (ref "M1") (pin "142") (pinfunction "CAM0_C_P_142") (pintype "input+no_connect"))
    )
    (net (code "154") (name "unconnected-(M1A-CAM0_D0_N-Pad128)") (class "Default")
      (node (ref "M1") (pin "128") (pinfunction "CAM0_D0_N_128") (pintype "input+no_connect"))
    )
    (net (code "155") (name "unconnected-(M1A-CAM0_D0_P-Pad130)") (class "Default")
      (node (ref "M1") (pin "130") (pinfunction "CAM0_D0_P_130") (pintype "input+no_connect"))
    )
    (net (code "156") (name "unconnected-(M1A-CAM0_D1_N-Pad134)") (class "Default")
      (node (ref "M1") (pin "134") (pinfunction "CAM0_D1_N_134") (pintype "input+no_connect"))
    )
    (net (code "157") (name "unconnected-(M1A-CAM0_D1_P-Pad136)") (class "Default")
      (node (ref "M1") (pin "136") (pinfunction "CAM0_D1_P_136") (pintype "input+no_connect"))
    )
    (net (code "158") (name "unconnected-(M1A-CAM1_C_N-Pad127)") (class "Default")
      (node (ref "M1") (pin "127") (pinfunction "CAM1_C_N_127") (pintype "input+no_connect"))
    )
    (net (code "159") (name "unconnected-(M1A-CAM1_C_P-Pad129)") (class "Default")
      (node (ref "M1") (pin "129") (pinfunction "CAM1_C_P_129") (pintype "input+no_connect"))
    )
    (net (code "160") (name "unconnected-(M1A-CAM1_D0_N-Pad115)") (class "Default")
      (node (ref "M1") (pin "115") (pinfunction "CAM1_D0_N_115") (pintype "input+no_connect"))
    )
    (net (code "161") (name "unconnected-(M1A-CAM1_D0_P-Pad117)") (class "Default")
      (node (ref "M1") (pin "117") (pinfunction "CAM1_D0_P_117") (pintype "input+no_connect"))
    )
    (net (code "162") (name "unconnected-(M1A-CAM1_D1_N-Pad121)") (class "Default")
      (node (ref "M1") (pin "121") (pinfunction "CAM1_D1_N_121") (pintype "input+no_connect"))
    )
    (net (code "163") (name "unconnected-(M1A-CAM1_D1_P-Pad123)") (class "Default")
      (node (ref "M1") (pin "123") (pinfunction "CAM1_D1_P_123") (pintype "input+no_connect"))
    )
    (net (code "164") (name "unconnected-(M1A-CAM1_D2_N-Pad133)") (class "Default")
      (node (ref "M1") (pin "133") (pinfunction "CAM1_D2_N_133") (pintype "input+no_connect"))
    )
    (net (code "165") (name "unconnected-(M1A-CAM1_D2_P-Pad135)") (class "Default")
      (node (ref "M1") (pin "135") (pinfunction "CAM1_D2_P_135") (pintype "input+no_connect"))
    )
    (net (code "166") (name "unconnected-(M1A-CAM1_D3_N-Pad139)") (class "Default")
      (node (ref "M1") (pin "139") (pinfunction "CAM1_D3_N_139") (pintype "input+no_connect"))
    )
    (net (code "167") (name "unconnected-(M1A-CAM1_D3_P-Pad141)") (class "Default")
      (node (ref "M1") (pin "141") (pinfunction "CAM1_D3_P_141") (pintype "input+no_connect"))
    )
    (net (code "168") (name "unconnected-(M1A-DSI0_C_N-Pad169)") (class "Default")
      (node (ref "M1") (pin "169") (pinfunction "DSI0_C_N_169") (pintype "output+no_connect"))
    )
    (net (code "169") (name "unconnected-(M1A-DSI0_C_P-Pad171)") (class "Default")
      (node (ref "M1") (pin "171") (pinfunction "DSI0_C_P_171") (pintype "output+no_connect"))
    )
    (net (code "170") (name "unconnected-(M1A-DSI0_D0_N-Pad157)") (class "Default")
      (node (ref "M1") (pin "157") (pinfunction "DSI0_D0_N_157") (pintype "output+no_connect"))
    )
    (net (code "171") (name "unconnected-(M1A-DSI0_D0_P-Pad159)") (class "Default")
      (node (ref "M1") (pin "159") (pinfunction "DSI0_D0_P_159") (pintype "output+no_connect"))
    )
    (net (code "172") (name "unconnected-(M1A-DSI0_D1_N-Pad163)") (class "Default")
      (node (ref "M1") (pin "163") (pinfunction "DSI0_D1_N_163") (pintype "output+no_connect"))
    )
    (net (code "173") (name "unconnected-(M1A-DSI0_D1_P-Pad165)") (class "Default")
      (node (ref "M1") (pin "165") (pinfunction "DSI0_D1_P_165") (pintype "output+no_connect"))
    )
    (net (code "174") (name "unconnected-(M1A-DSI1_C_N-Pad187)") (class "Default")
      (node (ref "M1") (pin "187") (pinfunction "DSI1_C_N_187") (pintype "output+no_connect"))
    )
    (net (code "175") (name "unconnected-(M1A-DSI1_C_P-Pad189)") (class "Default")
      (node (ref "M1") (pin "189") (pinfunction "DSI1_C_P_189") (pintype "output+no_connect"))
    )
    (net (code "176") (name "unconnected-(M1A-DSI1_D0_N-Pad175)") (class "Default")
      (node (ref "M1") (pin "175") (pinfunction "DSI1_D0_N_175") (pintype "output+no_connect"))
    )
    (net (code "177") (name "unconnected-(M1A-DSI1_D0_P-Pad177)") (class "Default")
      (node (ref "M1") (pin "177") (pinfunction "DSI1_D0_P_177") (pintype "output+no_connect"))
    )
    (net (code "178") (name "unconnected-(M1A-DSI1_D1_N-Pad181)") (class "Default")
      (node (ref "M1") (pin "181") (pinfunction "DSI1_D1_N_181") (pintype "output+no_connect"))
    )
    (net (code "179") (name "unconnected-(M1A-DSI1_D1_P-Pad183)") (class "Default")
      (node (ref "M1") (pin "183") (pinfunction "DSI1_D1_P_183") (pintype "output+no_connect"))
    )
    (net (code "180") (name "unconnected-(M1A-DSI1_D2_N-Pad193)") (class "Default")
      (node (ref "M1") (pin "193") (pinfunction "DSI1_D2_N_193") (pintype "output+no_connect"))
    )
    (net (code "181") (name "unconnected-(M1A-DSI1_D2_P-Pad195)") (class "Default")
      (node (ref "M1") (pin "195") (pinfunction "DSI1_D2_P_195") (pintype "output+no_connect"))
    )
    (net (code "182") (name "unconnected-(M1A-DSI1_D3_N-Pad194)") (class "Default")
      (node (ref "M1") (pin "194") (pinfunction "DSI1_D3_N_194") (pintype "output+no_connect"))
    )
    (net (code "183") (name "unconnected-(M1A-DSI1_D3_P-Pad196)") (class "Default")
      (node (ref "M1") (pin "196") (pinfunction "DSI1_D3_P_196") (pintype "output+no_connect"))
    )
    (net (code "184") (name "unconnected-(M1A-PCIE_!RST-Pad109)") (class "Default")
      (node (ref "M1") (pin "109") (pinfunction "PCIE_!RST_109") (pintype "output+no_connect"))
    )
    (net (code "185") (name "unconnected-(M1A-PCIE_CLK_!REQ-Pad102)") (class "Default")
      (node (ref "M1") (pin "102") (pinfunction "PCIE_CLK_!REQ_102") (pintype "input+no_connect"))
    )
    (net (code "186") (name "unconnected-(M1A-PCIE_CLK_N-Pad112)") (class "Default")
      (node (ref "M1") (pin "112") (pinfunction "PCIE_CLK_N_112") (pintype "output+no_connect"))
    )
    (net (code "187") (name "unconnected-(M1A-PCIE_CLK_P-Pad110)") (class "Default")
      (node (ref "M1") (pin "110") (pinfunction "PCIE_CLK_P_110") (pintype "output+no_connect"))
    )
    (net (code "188") (name "unconnected-(M1A-PCIE_RX_N-Pad118)") (class "Default")
      (node (ref "M1") (pin "118") (pinfunction "PCIE_RX_N_118") (pintype "input+no_connect"))
    )
    (net (code "189") (name "unconnected-(M1A-PCIE_RX_P-Pad116)") (class "Default")
      (node (ref "M1") (pin "116") (pinfunction "PCIE_RX_P_116") (pintype "input+no_connect"))
    )
    (net (code "190") (name "unconnected-(M1A-PCIE_TX_N-Pad124)") (class "Default")
      (node (ref "M1") (pin "124") (pinfunction "PCIE_TX_N_124") (pintype "output+no_connect"))
    )
    (net (code "191") (name "unconnected-(M1A-PCIE_TX_P-Pad122)") (class "Default")
      (node (ref "M1") (pin "122") (pinfunction "PCIE_TX_P_122") (pintype "output+no_connect"))
    )
    (net (code "192") (name "unconnected-(M1B-CAMERA_GPIO-Pad97)") (class "Default")
      (node (ref "M1") (pin "97") (pinfunction "CAMERA_GPIO_97") (pintype "bidirectional+no_connect"))
    )
    (net (code "193") (name "unconnected-(M1B-ETHERNET_!LED1-Pad19)") (class "Default")
      (node (ref "M1") (pin "19") (pinfunction "ETHERNET_!LED1_19") (pintype "output+no_connect"))
    )
    (net (code "194") (name "unconnected-(M1B-RESERVED-Pad76)") (class "Default")
      (node (ref "M1") (pin "76") (pinfunction "RESERVED_76") (pintype "passive+no_connect"))
    )
    (net (code "195") (name "unconnected-(M1B-RESERVED-Pad104)") (class "Default")
      (node (ref "M1") (pin "104") (pinfunction "RESERVED_104") (pintype "passive+no_connect"))
    )
    (net (code "196") (name "unconnected-(M1B-RESERVED-Pad106)") (class "Default")
      (node (ref "M1") (pin "106") (pinfunction "RESERVED_106") (pintype "passive+no_connect"))
    )
    (net (code "197") (name "unconnected-(M1B-SD_DAT4-Pad68)") (class "Default")
      (node (ref "M1") (pin "68") (pinfunction "SD_DAT4_68") (pintype "bidirectional+no_connect"))
    )
    (net (code "198") (name "unconnected-(M1B-SD_DAT5-Pad64)") (class "Default")
      (node (ref "M1") (pin "64") (pinfunction "SD_DAT5_64") (pintype "bidirectional+no_connect"))
    )
    (net (code "199") (name "unconnected-(M1B-SD_DAT6-Pad72)") (class "Default")
      (node (ref "M1") (pin "72") (pinfunction "SD_DAT6_72") (pintype "bidirectional+no_connect"))
    )
    (net (code "200") (name "unconnected-(M1B-SD_DAT7-Pad70)") (class "Default")
      (node (ref "M1") (pin "70") (pinfunction "SD_DAT7_70") (pintype "bidirectional+no_connect"))
    )
    (net (code "201") (name "unconnected-(M1B-SD_VDD_OVERRIDE-Pad73)") (class "Default")
      (node (ref "M1") (pin "73") (pinfunction "SD_VDD_OVERRIDE_73") (pintype "input+no_connect"))
    )
    (net (code "202") (name "unconnected-(MicroSD1-CD-Pad9)") (class "Default")
      (node (ref "MicroSD1") (pin "9") (pinfunction "CD_9") (pintype "passive"))
    )
    (net (code "203") (name "unconnected-(RJ？-NC-Pad7)") (class "Default")
      (node (ref "RJ？") (pin "7") (pinfunction "NC_7") (pintype "passive+no_connect"))
    )
    (net (code "204") (name "unconnected-(U1-CRFILT-Pad14)") (class "Default")
      (node (ref "U1") (pin "14") (pinfunction "CRFILT_14") (pintype "bidirectional+no_connect"))
    )
    (net (code "205") (name "unconnected-(U1-PLLFILT-Pad34)") (class "Default")
      (node (ref "U1") (pin "34") (pinfunction "PLLFILT_34") (pintype "bidirectional+no_connect"))
    )
    (net (code "206") (name "unconnected-(U1-PRTPWR1-Pad12)") (class "Default")
      (node (ref "U1") (pin "12") (pinfunction "PRTPWR1_12") (pintype "bidirectional"))
    )
    (net (code "207") (name "unconnected-(U1-PRTPWR2-Pad16)") (class "Default")
      (node (ref "U1") (pin "16") (pinfunction "PRTPWR2_16") (pintype "bidirectional"))
    )
    (net (code "208") (name "unconnected-(U1-PRTPWR3-Pad18)") (class "Default")
      (node (ref "U1") (pin "18") (pinfunction "PRTPWR3_18") (pintype "bidirectional"))
    )
    (net (code "209") (name "unconnected-(U1-PRTPWR4-Pad20)") (class "Default")
      (node (ref "U1") (pin "20") (pinfunction "PRTPWR4_20") (pintype "bidirectional"))
    )
    (net (code "210") (name "unconnected-(U1-TEST-Pad11)") (class "Default")
      (node (ref "U1") (pin "11") (pinfunction "TEST_11") (pintype "bidirectional+no_connect"))
    )
    (net (code "211") (name "unconnected-(U7-CLK-Pad7)") (class "Default")
      (node (ref "U7") (pin "7") (pinfunction "CLK_7") (pintype "passive+no_connect"))
    )
    (net (code "212") (name "unconnected-(U7-nALERT-Pad8)") (class "Default")
      (node (ref "U7") (pin "8") (pinfunction "nALERT_8") (pintype "passive+no_connect"))
    )
  )
)
